# 8_Motors_sch.net
KiCad netlist of a schematic drawn in Altium Designer
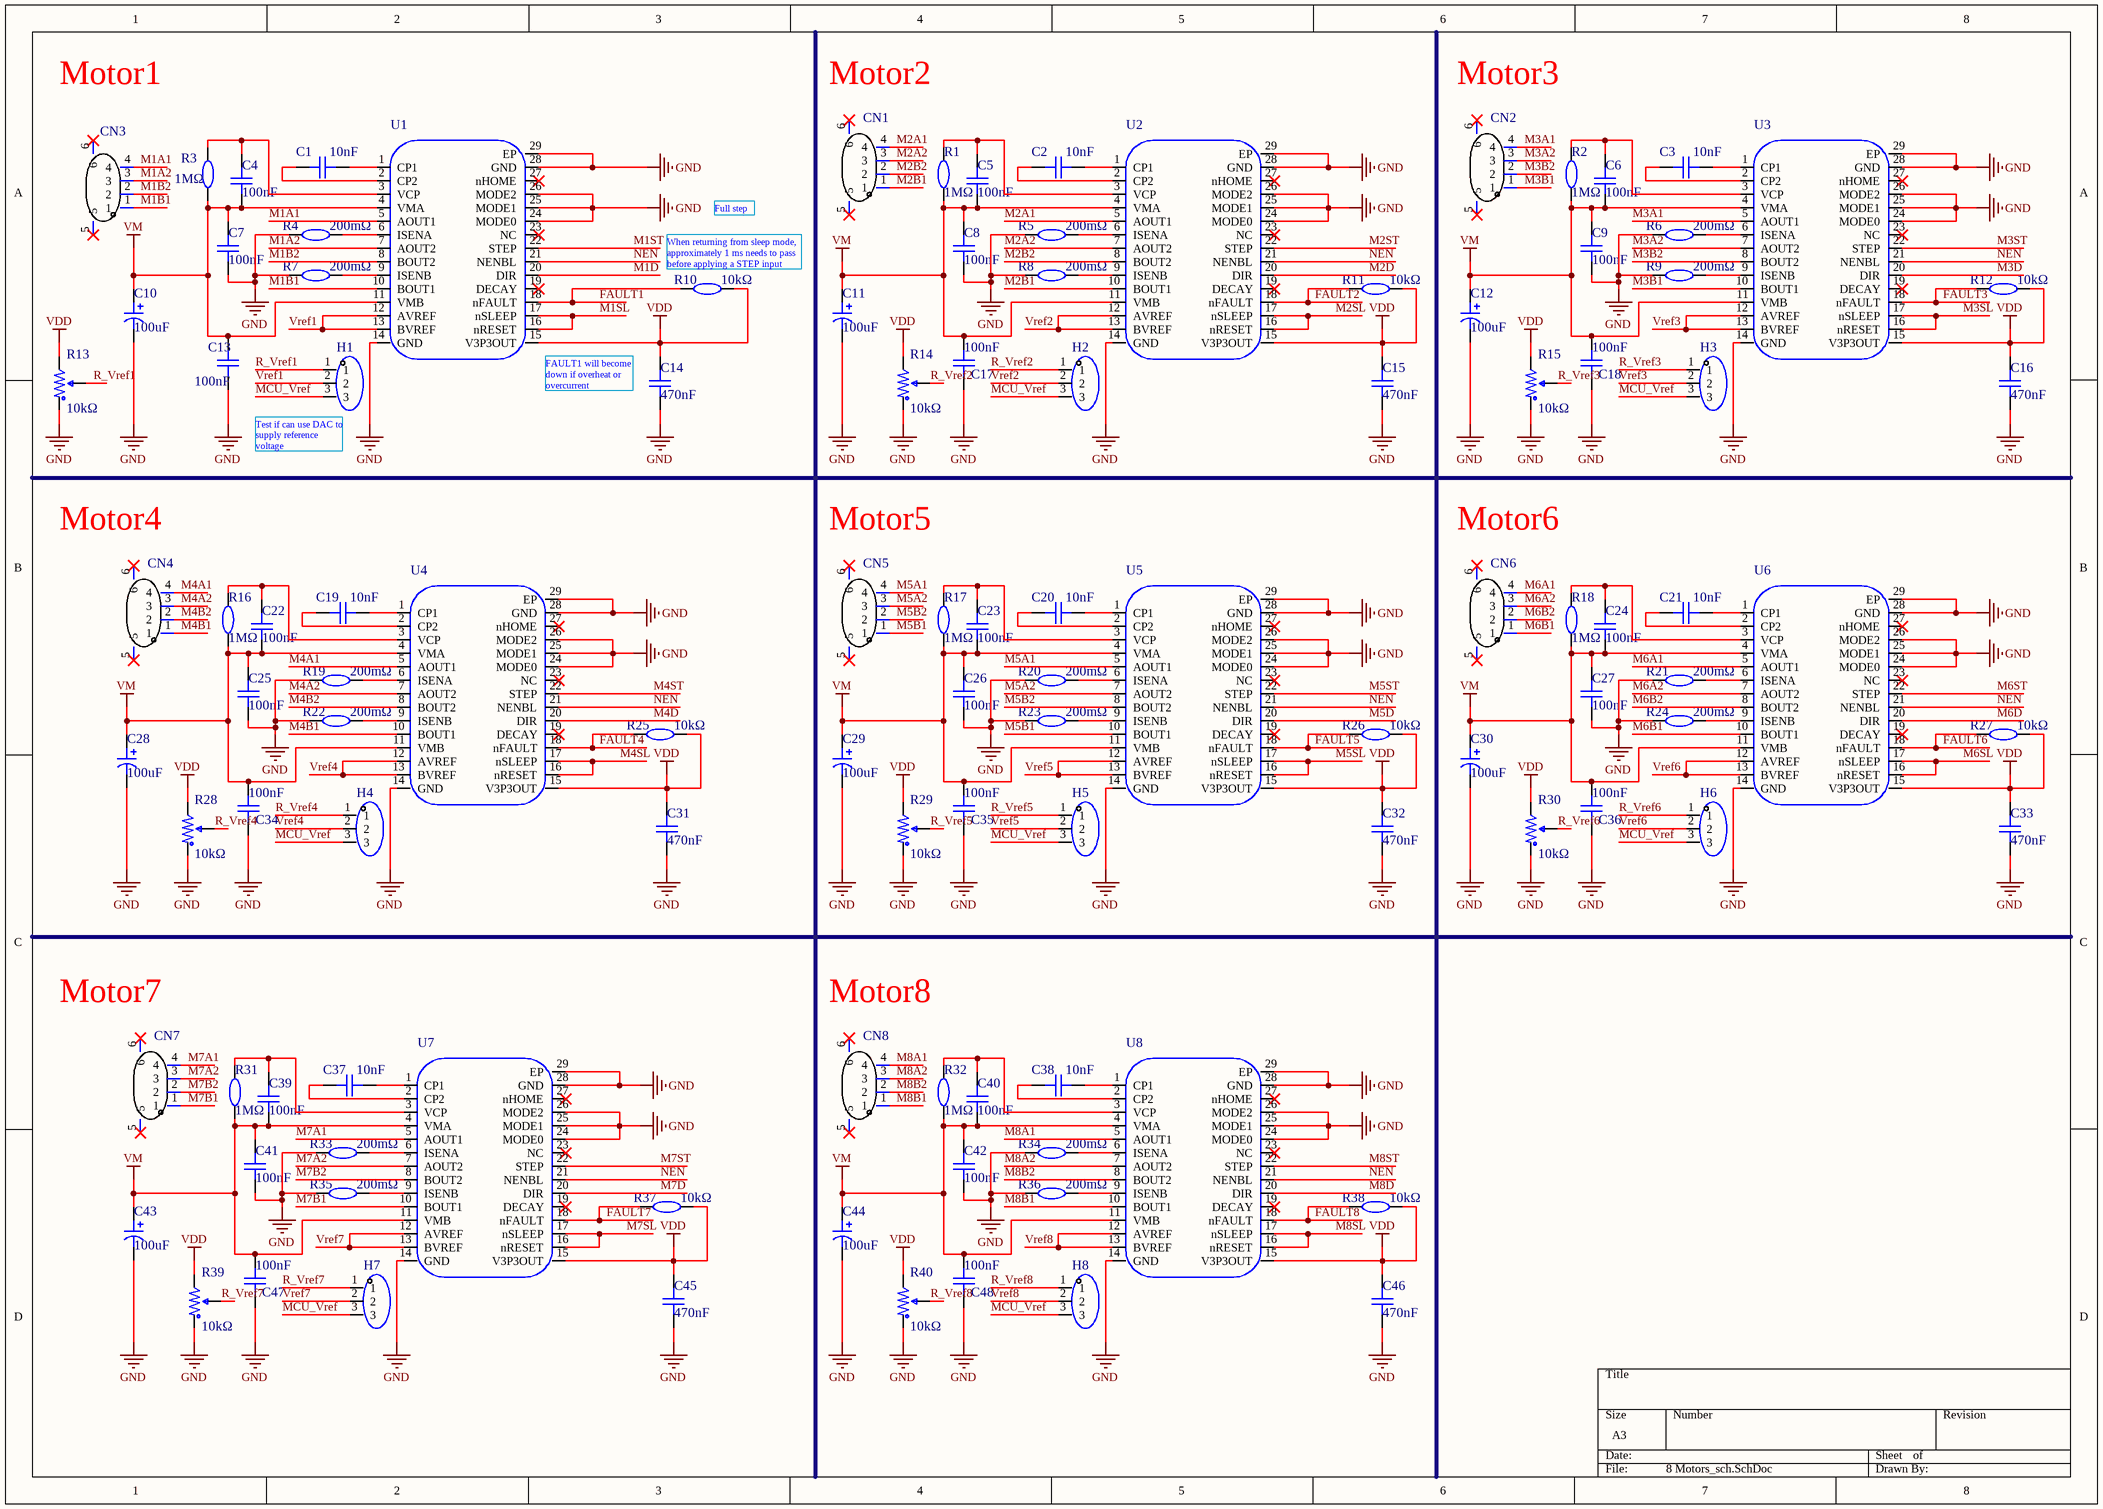
[diagram p0: 8 Motors_sch.SchDoc]

(export (version "E")
  (design (tool "Eeschema 10.0.6"))
  (components
    (comp (ref "C1")
      (value "10nF")
      (footprint "C0603")
      (description "0603电容")
      (fields
        (field (name "MANUFACTURER") "SAMSUNG(三星)")
        (field (name "MANUFACTURER PART") "CC0603KRX7R9BB104")
      )
      (libsource (lib "SchLib") (part "C0603_10nF"))
    )
    (comp (ref "C2")
      (value "10nF")
      (footprint "C0603")
      (description "0603电容")
      (fields
        (field (name "MANUFACTURER") "SAMSUNG(三星)")
        (field (name "MANUFACTURER PART") "CC0603KRX7R9BB104")
      )
      (libsource (lib "SchLib") (part "C0603_10nF"))
    )
    (comp (ref "C3")
      (value "10nF")
      (footprint "C0603")
      (description "0603电容")
      (fields
        (field (name "MANUFACTURER") "SAMSUNG(三星)")
        (field (name "MANUFACTURER PART") "CC0603KRX7R9BB104")
      )
      (libsource (lib "SchLib") (part "C0603_10nF"))
    )
    (comp (ref "C4")
      (value "100nF")
      (footprint "C0603")
      (description "0603电容")
      (fields
        (field (name "MANUFACTURER") "SAMSUNG(三星)")
        (field (name "MANUFACTURER PART") "CC0603KRX7R9BB104")
      )
      (libsource (lib "SchLib") (part "C0603_100nF"))
    )
    (comp (ref "C5")
      (value "100nF")
      (footprint "C0603")
      (description "0603电容")
      (fields
        (field (name "MANUFACTURER") "SAMSUNG(三星)")
        (field (name "MANUFACTURER PART") "CC0603KRX7R9BB104")
      )
      (libsource (lib "SchLib") (part "C0603_100nF"))
    )
    (comp (ref "C6")
      (value "100nF")
      (footprint "C0603")
      (description "0603电容")
      (fields
        (field (name "MANUFACTURER") "SAMSUNG(三星)")
        (field (name "MANUFACTURER PART") "CC0603KRX7R9BB104")
      )
      (libsource (lib "SchLib") (part "C0603_100nF"))
    )
    (comp (ref "C7")
      (value "100nF")
      (footprint "C0603")
      (description "0603电容")
      (fields
        (field (name "MANUFACTURER") "SAMSUNG(三星)")
        (field (name "MANUFACTURER PART") "CC0603KRX7R9BB104")
      )
      (libsource (lib "SchLib") (part "C0603_100nF"))
    )
    (comp (ref "C8")
      (value "100nF")
      (footprint "C0603")
      (description "0603电容")
      (fields
        (field (name "MANUFACTURER") "SAMSUNG(三星)")
        (field (name "MANUFACTURER PART") "CC0603KRX7R9BB104")
      )
      (libsource (lib "SchLib") (part "C0603_100nF"))
    )
    (comp (ref "C9")
      (value "100nF")
      (footprint "C0603")
      (description "0603电容")
      (fields
        (field (name "MANUFACTURER") "SAMSUNG(三星)")
        (field (name "MANUFACTURER PART") "CC0603KRX7R9BB104")
      )
      (libsource (lib "SchLib") (part "C0603_100nF"))
    )
    (comp (ref "C10")
      (value "100uF")
      (footprint "SMD6.3_7.7_100uF")
      (description "贴片型铝电解电容 容值 100uF 精度 ±20% 额定电压 35V 纹波电流 87mA@120kHz")
      (fields
        (field (name "MANUFACTURER") "KNSCHA(科尼盛)")
        (field (name "MANUFACTURER PART") "RVT100UF35V67RV0034")
      )
      (libsource (lib "SchLib") (part "SMD6.3_7.7_100uF"))
    )
    (comp (ref "C11")
      (value "100uF")
      (footprint "SMD6.3_7.7_100uF")
      (description "贴片型铝电解电容 容值 100uF 精度 ±20% 额定电压 35V 纹波电流 87mA@120kHz")
      (fields
        (field (name "MANUFACTURER") "KNSCHA(科尼盛)")
        (field (name "MANUFACTURER PART") "RVT100UF35V67RV0034")
      )
      (libsource (lib "SchLib") (part "SMD6.3_7.7_100uF"))
    )
    (comp (ref "C12")
      (value "100uF")
      (footprint "SMD6.3_7.7_100uF")
      (description "贴片型铝电解电容 容值 100uF 精度 ±20% 额定电压 35V 纹波电流 87mA@120kHz")
      (fields
        (field (name "MANUFACTURER") "KNSCHA(科尼盛)")
        (field (name "MANUFACTURER PART") "RVT100UF35V67RV0034")
      )
      (libsource (lib "SchLib") (part "SMD6.3_7.7_100uF"))
    )
    (comp (ref "C13")
      (value "100nF")
      (footprint "C0603")
      (description "0603电容")
      (fields
        (field (name "MANUFACTURER") "SAMSUNG(三星)")
        (field (name "MANUFACTURER PART") "CC0603KRX7R9BB104")
      )
      (libsource (lib "SchLib") (part "C0603_100nF"))
    )
    (comp (ref "C14")
      (value "470nF")
      (footprint "C0603")
      (description "0603电容")
      (fields
        (field (name "MANUFACTURER") "SAMSUNG(三星)")
        (field (name "MANUFACTURER PART") "CC0603KRX7R9BB104")
      )
      (libsource (lib "SchLib") (part "C0603_470nF"))
    )
    (comp (ref "C15")
      (value "470nF")
      (footprint "C0603")
      (description "0603电容")
      (fields
        (field (name "MANUFACTURER") "SAMSUNG(三星)")
        (field (name "MANUFACTURER PART") "CC0603KRX7R9BB104")
      )
      (libsource (lib "SchLib") (part "C0603_470nF"))
    )
    (comp (ref "C16")
      (value "470nF")
      (footprint "C0603")
      (description "0603电容")
      (fields
        (field (name "MANUFACTURER") "SAMSUNG(三星)")
        (field (name "MANUFACTURER PART") "CC0603KRX7R9BB104")
      )
      (libsource (lib "SchLib") (part "C0603_470nF"))
    )
    (comp (ref "C17")
      (value "100nF")
      (footprint "C0603")
      (description "0603电容")
      (fields
        (field (name "MANUFACTURER") "SAMSUNG(三星)")
        (field (name "MANUFACTURER PART") "CC0603KRX7R9BB104")
      )
      (libsource (lib "SchLib") (part "C0603_100nF"))
    )
    (comp (ref "C18")
      (value "100nF")
      (footprint "C0603")
      (description "0603电容")
      (fields
        (field (name "MANUFACTURER") "SAMSUNG(三星)")
        (field (name "MANUFACTURER PART") "CC0603KRX7R9BB104")
      )
      (libsource (lib "SchLib") (part "C0603_100nF"))
    )
    (comp (ref "C19")
      (value "10nF")
      (footprint "C0603")
      (description "0603电容")
      (fields
        (field (name "MANUFACTURER") "SAMSUNG(三星)")
        (field (name "MANUFACTURER PART") "CC0603KRX7R9BB104")
      )
      (libsource (lib "SchLib") (part "C0603_10nF"))
    )
    (comp (ref "C20")
      (value "10nF")
      (footprint "C0603")
      (description "0603电容")
      (fields
        (field (name "MANUFACTURER") "SAMSUNG(三星)")
        (field (name "MANUFACTURER PART") "CC0603KRX7R9BB104")
      )
      (libsource (lib "SchLib") (part "C0603_10nF"))
    )
    (comp (ref "C21")
      (value "10nF")
      (footprint "C0603")
      (description "0603电容")
      (fields
        (field (name "MANUFACTURER") "SAMSUNG(三星)")
        (field (name "MANUFACTURER PART") "CC0603KRX7R9BB104")
      )
      (libsource (lib "SchLib") (part "C0603_10nF"))
    )
    (comp (ref "C22")
      (value "100nF")
      (footprint "C0603")
      (description "0603电容")
      (fields
        (field (name "MANUFACTURER") "SAMSUNG(三星)")
        (field (name "MANUFACTURER PART") "CC0603KRX7R9BB104")
      )
      (libsource (lib "SchLib") (part "C0603_100nF"))
    )
    (comp (ref "C23")
      (value "100nF")
      (footprint "C0603")
      (description "0603电容")
      (fields
        (field (name "MANUFACTURER") "SAMSUNG(三星)")
        (field (name "MANUFACTURER PART") "CC0603KRX7R9BB104")
      )
      (libsource (lib "SchLib") (part "C0603_100nF"))
    )
    (comp (ref "C24")
      (value "100nF")
      (footprint "C0603")
      (description "0603电容")
      (fields
        (field (name "MANUFACTURER") "SAMSUNG(三星)")
        (field (name "MANUFACTURER PART") "CC0603KRX7R9BB104")
      )
      (libsource (lib "SchLib") (part "C0603_100nF"))
    )
    (comp (ref "C25")
      (value "100nF")
      (footprint "C0603")
      (description "0603电容")
      (fields
        (field (name "MANUFACTURER") "SAMSUNG(三星)")
        (field (name "MANUFACTURER PART") "CC0603KRX7R9BB104")
      )
      (libsource (lib "SchLib") (part "C0603_100nF"))
    )
    (comp (ref "C26")
      (value "100nF")
      (footprint "C0603")
      (description "0603电容")
      (fields
        (field (name "MANUFACTURER") "SAMSUNG(三星)")
        (field (name "MANUFACTURER PART") "CC0603KRX7R9BB104")
      )
      (libsource (lib "SchLib") (part "C0603_100nF"))
    )
    (comp (ref "C27")
      (value "100nF")
      (footprint "C0603")
      (description "0603电容")
      (fields
        (field (name "MANUFACTURER") "SAMSUNG(三星)")
        (field (name "MANUFACTURER PART") "CC0603KRX7R9BB104")
      )
      (libsource (lib "SchLib") (part "C0603_100nF"))
    )
    (comp (ref "C28")
      (value "100uF")
      (footprint "SMD6.3_7.7_100uF")
      (description "贴片型铝电解电容 容值 100uF 精度 ±20% 额定电压 35V 纹波电流 87mA@120kHz")
      (fields
        (field (name "MANUFACTURER") "KNSCHA(科尼盛)")
        (field (name "MANUFACTURER PART") "RVT100UF35V67RV0034")
      )
      (libsource (lib "SchLib") (part "SMD6.3_7.7_100uF"))
    )
    (comp (ref "C29")
      (value "100uF")
      (footprint "SMD6.3_7.7_100uF")
      (description "贴片型铝电解电容 容值 100uF 精度 ±20% 额定电压 35V 纹波电流 87mA@120kHz")
      (fields
        (field (name "MANUFACTURER") "KNSCHA(科尼盛)")
        (field (name "MANUFACTURER PART") "RVT100UF35V67RV0034")
      )
      (libsource (lib "SchLib") (part "SMD6.3_7.7_100uF"))
    )
    (comp (ref "C30")
      (value "100uF")
      (footprint "SMD6.3_7.7_100uF")
      (description "贴片型铝电解电容 容值 100uF 精度 ±20% 额定电压 35V 纹波电流 87mA@120kHz")
      (fields
        (field (name "MANUFACTURER") "KNSCHA(科尼盛)")
        (field (name "MANUFACTURER PART") "RVT100UF35V67RV0034")
      )
      (libsource (lib "SchLib") (part "SMD6.3_7.7_100uF"))
    )
    (comp (ref "C31")
      (value "470nF")
      (footprint "C0603")
      (description "0603电容")
      (fields
        (field (name "MANUFACTURER") "SAMSUNG(三星)")
        (field (name "MANUFACTURER PART") "CC0603KRX7R9BB104")
      )
      (libsource (lib "SchLib") (part "C0603_470nF"))
    )
    (comp (ref "C32")
      (value "470nF")
      (footprint "C0603")
      (description "0603电容")
      (fields
        (field (name "MANUFACTURER") "SAMSUNG(三星)")
        (field (name "MANUFACTURER PART") "CC0603KRX7R9BB104")
      )
      (libsource (lib "SchLib") (part "C0603_470nF"))
    )
    (comp (ref "C33")
      (value "470nF")
      (footprint "C0603")
      (description "0603电容")
      (fields
        (field (name "MANUFACTURER") "SAMSUNG(三星)")
        (field (name "MANUFACTURER PART") "CC0603KRX7R9BB104")
      )
      (libsource (lib "SchLib") (part "C0603_470nF"))
    )
    (comp (ref "C34")
      (value "100nF")
      (footprint "C0603")
      (description "0603电容")
      (fields
        (field (name "MANUFACTURER") "SAMSUNG(三星)")
        (field (name "MANUFACTURER PART") "CC0603KRX7R9BB104")
      )
      (libsource (lib "SchLib") (part "C0603_100nF"))
    )
    (comp (ref "C35")
      (value "100nF")
      (footprint "C0603")
      (description "0603电容")
      (fields
        (field (name "MANUFACTURER") "SAMSUNG(三星)")
        (field (name "MANUFACTURER PART") "CC0603KRX7R9BB104")
      )
      (libsource (lib "SchLib") (part "C0603_100nF"))
    )
    (comp (ref "C36")
      (value "100nF")
      (footprint "C0603")
      (description "0603电容")
      (fields
        (field (name "MANUFACTURER") "SAMSUNG(三星)")
        (field (name "MANUFACTURER PART") "CC0603KRX7R9BB104")
      )
      (libsource (lib "SchLib") (part "C0603_100nF"))
    )
    (comp (ref "C37")
      (value "10nF")
      (footprint "C0603")
      (description "0603电容")
      (fields
        (field (name "MANUFACTURER") "SAMSUNG(三星)")
        (field (name "MANUFACTURER PART") "CC0603KRX7R9BB104")
      )
      (libsource (lib "SchLib") (part "C0603_10nF"))
    )
    (comp (ref "C38")
      (value "10nF")
      (footprint "C0603")
      (description "0603电容")
      (fields
        (field (name "MANUFACTURER") "SAMSUNG(三星)")
        (field (name "MANUFACTURER PART") "CC0603KRX7R9BB104")
      )
      (libsource (lib "SchLib") (part "C0603_10nF"))
    )
    (comp (ref "C39")
      (value "100nF")
      (footprint "C0603")
      (description "0603电容")
      (fields
        (field (name "MANUFACTURER") "SAMSUNG(三星)")
        (field (name "MANUFACTURER PART") "CC0603KRX7R9BB104")
      )
      (libsource (lib "SchLib") (part "C0603_100nF"))
    )
    (comp (ref "C40")
      (value "100nF")
      (footprint "C0603")
      (description "0603电容")
      (fields
        (field (name "MANUFACTURER") "SAMSUNG(三星)")
        (field (name "MANUFACTURER PART") "CC0603KRX7R9BB104")
      )
      (libsource (lib "SchLib") (part "C0603_100nF"))
    )
    (comp (ref "C41")
      (value "100nF")
      (footprint "C0603")
      (description "0603电容")
      (fields
        (field (name "MANUFACTURER") "SAMSUNG(三星)")
        (field (name "MANUFACTURER PART") "CC0603KRX7R9BB104")
      )
      (libsource (lib "SchLib") (part "C0603_100nF"))
    )
    (comp (ref "C42")
      (value "100nF")
      (footprint "C0603")
      (description "0603电容")
      (fields
        (field (name "MANUFACTURER") "SAMSUNG(三星)")
        (field (name "MANUFACTURER PART") "CC0603KRX7R9BB104")
      )
      (libsource (lib "SchLib") (part "C0603_100nF"))
    )
    (comp (ref "C43")
      (value "100uF")
      (footprint "SMD6.3_7.7_100uF")
      (description "贴片型铝电解电容 容值 100uF 精度 ±20% 额定电压 35V 纹波电流 87mA@120kHz")
      (fields
        (field (name "MANUFACTURER") "KNSCHA(科尼盛)")
        (field (name "MANUFACTURER PART") "RVT100UF35V67RV0034")
      )
      (libsource (lib "SchLib") (part "SMD6.3_7.7_100uF"))
    )
    (comp (ref "C44")
      (value "100uF")
      (footprint "SMD6.3_7.7_100uF")
      (description "贴片型铝电解电容 容值 100uF 精度 ±20% 额定电压 35V 纹波电流 87mA@120kHz")
      (fields
        (field (name "MANUFACTURER") "KNSCHA(科尼盛)")
        (field (name "MANUFACTURER PART") "RVT100UF35V67RV0034")
      )
      (libsource (lib "SchLib") (part "SMD6.3_7.7_100uF"))
    )
    (comp (ref "C45")
      (value "470nF")
      (footprint "C0603")
      (description "0603电容")
      (fields
        (field (name "MANUFACTURER") "SAMSUNG(三星)")
        (field (name "MANUFACTURER PART") "CC0603KRX7R9BB104")
      )
      (libsource (lib "SchLib") (part "C0603_470nF"))
    )
    (comp (ref "C46")
      (value "470nF")
      (footprint "C0603")
      (description "0603电容")
      (fields
        (field (name "MANUFACTURER") "SAMSUNG(三星)")
        (field (name "MANUFACTURER PART") "CC0603KRX7R9BB104")
      )
      (libsource (lib "SchLib") (part "C0603_470nF"))
    )
    (comp (ref "C47")
      (value "100nF")
      (footprint "C0603")
      (description "0603电容")
      (fields
        (field (name "MANUFACTURER") "SAMSUNG(三星)")
        (field (name "MANUFACTURER PART") "CC0603KRX7R9BB104")
      )
      (libsource (lib "SchLib") (part "C0603_100nF"))
    )
    (comp (ref "C48")
      (value "100nF")
      (footprint "C0603")
      (description "0603电容")
      (fields
        (field (name "MANUFACTURER") "SAMSUNG(三星)")
        (field (name "MANUFACTURER PART") "CC0603KRX7R9BB104")
      )
      (libsource (lib "SchLib") (part "C0603_100nF"))
    )
    (comp (ref "CN1")
      (value "HC-1.25-4PLT")
      (footprint "HC-1.25-4PLT")
      (description "插针结构: 1x4P  间距: 1.25mm  安装方式: 立贴  总PIN数: 4P")
      (fields (field (name "MANUFACTURER") "HCTL(华灿天禄)"))
      (libsource (lib "SchLib") (part "HC-1.25-4PLT"))
    )
    (comp (ref "CN2")
      (value "HC-1.25-4PLT")
      (footprint "HC-1.25-4PLT")
      (description "插针结构: 1x4P  间距: 1.25mm  安装方式: 立贴  总PIN数: 4P")
      (fields (field (name "MANUFACTURER") "HCTL(华灿天禄)"))
      (libsource (lib "SchLib") (part "HC-1.25-4PLT"))
    )
    (comp (ref "CN3")
      (value "HC-1.25-4PLT")
      (footprint "HC-1.25-4PLT")
      (description "插针结构: 1x4P  间距: 1.25mm  安装方式: 立贴  总PIN数: 4P")
      (fields (field (name "MANUFACTURER") "HCTL(华灿天禄)"))
      (libsource (lib "SchLib") (part "HC-1.25-4PLT"))
    )
    (comp (ref "CN4")
      (value "HC-1.25-4PLT")
      (footprint "HC-1.25-4PLT")
      (description "插针结构: 1x4P  间距: 1.25mm  安装方式: 立贴  总PIN数: 4P")
      (fields (field (name "MANUFACTURER") "HCTL(华灿天禄)"))
      (libsource (lib "SchLib") (part "HC-1.25-4PLT"))
    )
    (comp (ref "CN5")
      (value "HC-1.25-4PLT")
      (footprint "HC-1.25-4PLT")
      (description "插针结构: 1x4P  间距: 1.25mm  安装方式: 立贴  总PIN数: 4P")
      (fields (field (name "MANUFACTURER") "HCTL(华灿天禄)"))
      (libsource (lib "SchLib") (part "HC-1.25-4PLT"))
    )
    (comp (ref "CN6")
      (value "HC-1.25-4PLT")
      (footprint "HC-1.25-4PLT")
      (description "插针结构: 1x4P  间距: 1.25mm  安装方式: 立贴  总PIN数: 4P")
      (fields (field (name "MANUFACTURER") "HCTL(华灿天禄)"))
      (libsource (lib "SchLib") (part "HC-1.25-4PLT"))
    )
    (comp (ref "CN7")
      (value "HC-1.25-4PLT")
      (footprint "HC-1.25-4PLT")
      (description "插针结构: 1x4P  间距: 1.25mm  安装方式: 立贴  总PIN数: 4P")
      (fields (field (name "MANUFACTURER") "HCTL(华灿天禄)"))
      (libsource (lib "SchLib") (part "HC-1.25-4PLT"))
    )
    (comp (ref "CN8")
      (value "HC-1.25-4PLT")
      (footprint "HC-1.25-4PLT")
      (description "插针结构: 1x4P  间距: 1.25mm  安装方式: 立贴  总PIN数: 4P")
      (fields (field (name "MANUFACTURER") "HCTL(华灿天禄)"))
      (libsource (lib "SchLib") (part "HC-1.25-4PLT"))
    )
    (comp (ref "H1")
      (value "PZ254V-11-03P")
      (footprint "HC-1.25-3PLT")
      (description "排针3P")
      (fields (field (name "MANUFACTURER") "XFCN(兴飞)"))
      (libsource (lib "SchLib") (part "HC-1.25-3PLT"))
    )
    (comp (ref "H2")
      (value "PZ254V-11-03P")
      (footprint "HC-1.25-3PLT")
      (description "排针3P")
      (fields (field (name "MANUFACTURER") "XFCN(兴飞)"))
      (libsource (lib "SchLib") (part "HC-1.25-3PLT"))
    )
    (comp (ref "H3")
      (value "PZ254V-11-03P")
      (footprint "HC-1.25-3PLT")
      (description "排针3P")
      (fields (field (name "MANUFACTURER") "XFCN(兴飞)"))
      (libsource (lib "SchLib") (part "HC-1.25-3PLT"))
    )
    (comp (ref "H4")
      (value "PZ254V-11-03P")
      (footprint "HC-1.25-3PLT")
      (description "排针3P")
      (fields (field (name "MANUFACTURER") "XFCN(兴飞)"))
      (libsource (lib "SchLib") (part "HC-1.25-3PLT"))
    )
    (comp (ref "H5")
      (value "PZ254V-11-03P")
      (footprint "HC-1.25-3PLT")
      (description "排针3P")
      (fields (field (name "MANUFACTURER") "XFCN(兴飞)"))
      (libsource (lib "SchLib") (part "HC-1.25-3PLT"))
    )
    (comp (ref "H6")
      (value "PZ254V-11-03P")
      (footprint "HC-1.25-3PLT")
      (description "排针3P")
      (fields (field (name "MANUFACTURER") "XFCN(兴飞)"))
      (libsource (lib "SchLib") (part "HC-1.25-3PLT"))
    )
    (comp (ref "H7")
      (value "PZ254V-11-03P")
      (footprint "HC-1.25-3PLT")
      (description "排针3P")
      (fields (field (name "MANUFACTURER") "XFCN(兴飞)"))
      (libsource (lib "SchLib") (part "HC-1.25-3PLT"))
    )
    (comp (ref "H8")
      (value "PZ254V-11-03P")
      (footprint "HC-1.25-3PLT")
      (description "排针3P")
      (fields (field (name "MANUFACTURER") "XFCN(兴飞)"))
      (libsource (lib "SchLib") (part "HC-1.25-3PLT"))
    )
    (comp (ref "R1")
      (value "1MΩ")
      (footprint "R0603")
      (description "0603电阻")
      (fields
        (field (name "MANUFACTURER") "UNI-ROYAL(厚声)")
        (field (name "MANUFACTURER PART") "0603WAF5100T5E")
      )
      (libsource (lib "SchLib") (part "R0603_1MΩ"))
    )
    (comp (ref "R2")
      (value "1MΩ")
      (footprint "R0603")
      (description "0603电阻")
      (fields
        (field (name "MANUFACTURER") "UNI-ROYAL(厚声)")
        (field (name "MANUFACTURER PART") "0603WAF5100T5E")
      )
      (libsource (lib "SchLib") (part "R0603_1MΩ"))
    )
    (comp (ref "R3")
      (value "1MΩ")
      (footprint "R0603")
      (description "0603电阻")
      (fields
        (field (name "MANUFACTURER") "UNI-ROYAL(厚声)")
        (field (name "MANUFACTURER PART") "0603WAF5100T5E")
      )
      (libsource (lib "SchLib") (part "R0603_1MΩ"))
    )
    (comp (ref "R4")
      (value "200mΩ")
      (footprint "R1206_200mΩ")
      (description "1206电阻")
      (fields
        (field (name "MANUFACTURER") "UNI-ROYAL(厚声)")
        (field (name "MANUFACTURER PART") "1206W4F200LT5E")
      )
      (libsource (lib "SchLib") (part "R1206_200mΩ"))
    )
    (comp (ref "R5")
      (value "200mΩ")
      (footprint "R1206_200mΩ")
      (description "1206电阻")
      (fields
        (field (name "MANUFACTURER") "UNI-ROYAL(厚声)")
        (field (name "MANUFACTURER PART") "1206W4F200LT5E")
      )
      (libsource (lib "SchLib") (part "R1206_200mΩ"))
    )
    (comp (ref "R6")
      (value "200mΩ")
      (footprint "R1206_200mΩ")
      (description "1206电阻")
      (fields
        (field (name "MANUFACTURER") "UNI-ROYAL(厚声)")
        (field (name "MANUFACTURER PART") "1206W4F200LT5E")
      )
      (libsource (lib "SchLib") (part "R1206_200mΩ"))
    )
    (comp (ref "R7")
      (value "200mΩ")
      (footprint "R1206_200mΩ")
      (description "1206电阻")
      (fields
        (field (name "MANUFACTURER") "UNI-ROYAL(厚声)")
        (field (name "MANUFACTURER PART") "1206W4F200LT5E")
      )
      (libsource (lib "SchLib") (part "R1206_200mΩ"))
    )
    (comp (ref "R8")
      (value "200mΩ")
      (footprint "R1206_200mΩ")
      (description "1206电阻")
      (fields
        (field (name "MANUFACTURER") "UNI-ROYAL(厚声)")
        (field (name "MANUFACTURER PART") "1206W4F200LT5E")
      )
      (libsource (lib "SchLib") (part "R1206_200mΩ"))
    )
    (comp (ref "R9")
      (value "200mΩ")
      (footprint "R1206_200mΩ")
      (description "1206电阻")
      (fields
        (field (name "MANUFACTURER") "UNI-ROYAL(厚声)")
        (field (name "MANUFACTURER PART") "1206W4F200LT5E")
      )
      (libsource (lib "SchLib") (part "R1206_200mΩ"))
    )
    (comp (ref "R10")
      (value "10kΩ")
      (footprint "R0603_10KΩ")
      (description "0603电阻")
      (fields
        (field (name "MANUFACTURER") "UNI-ROYAL(厚声)")
        (field (name "MANUFACTURER PART") "0603WAF1002T5E")
      )
      (libsource (lib "SchLib") (part "R0603_10KΩ"))
    )
    (comp (ref "R11")
      (value "10kΩ")
      (footprint "R0603_10KΩ")
      (description "0603电阻")
      (fields
        (field (name "MANUFACTURER") "UNI-ROYAL(厚声)")
        (field (name "MANUFACTURER PART") "0603WAF1002T5E")
      )
      (libsource (lib "SchLib") (part "R0603_10KΩ"))
    )
    (comp (ref "R12")
      (value "10kΩ")
      (footprint "R0603_10KΩ")
      (description "0603电阻")
      (fields
        (field (name "MANUFACTURER") "UNI-ROYAL(厚声)")
        (field (name "MANUFACTURER PART") "0603WAF1002T5E")
      )
      (libsource (lib "SchLib") (part "R0603_10KΩ"))
    )
    (comp (ref "R13")
      (value "10kΩ")
      (footprint "R10k_KT")
      (description "可调电阻/电位器   阻值 10kΩ   精度 ±25%   额定电压 -   功率 150mW   温度系数 ±250ppm/℃   圈数 1")
      (fields (field (name "MANUFACTURER") "BOURNS") (field (name "MANUFACTURER PART") "TC33X-2-103E"))
      (libsource (lib "SchLib") (part "R10k_KT"))
    )
    (comp (ref "R14")
      (value "10kΩ")
      (footprint "R10k_KT")
      (description "可调电阻/电位器   阻值 10kΩ   精度 ±25%   额定电压 -   功率 150mW   温度系数 ±250ppm/℃   圈数 1")
      (fields (field (name "MANUFACTURER") "BOURNS") (field (name "MANUFACTURER PART") "TC33X-2-103E"))
      (libsource (lib "SchLib") (part "R10k_KT"))
    )
    (comp (ref "R15")
      (value "10kΩ")
      (footprint "R10k_KT")
      (description "可调电阻/电位器   阻值 10kΩ   精度 ±25%   额定电压 -   功率 150mW   温度系数 ±250ppm/℃   圈数 1")
      (fields (field (name "MANUFACTURER") "BOURNS") (field (name "MANUFACTURER PART") "TC33X-2-103E"))
      (libsource (lib "SchLib") (part "R10k_KT"))
    )
    (comp (ref "R16")
      (value "1MΩ")
      (footprint "R0603")
      (description "0603电阻")
      (fields
        (field (name "MANUFACTURER") "UNI-ROYAL(厚声)")
        (field (name "MANUFACTURER PART") "0603WAF5100T5E")
      )
      (libsource (lib "SchLib") (part "R0603_1MΩ"))
    )
    (comp (ref "R17")
      (value "1MΩ")
      (footprint "R0603")
      (description "0603电阻")
      (fields
        (field (name "MANUFACTURER") "UNI-ROYAL(厚声)")
        (field (name "MANUFACTURER PART") "0603WAF5100T5E")
      )
      (libsource (lib "SchLib") (part "R0603_1MΩ"))
    )
    (comp (ref "R18")
      (value "1MΩ")
      (footprint "R0603")
      (description "0603电阻")
      (fields
        (field (name "MANUFACTURER") "UNI-ROYAL(厚声)")
        (field (name "MANUFACTURER PART") "0603WAF5100T5E")
      )
      (libsource (lib "SchLib") (part "R0603_1MΩ"))
    )
    (comp (ref "R19")
      (value "200mΩ")
      (footprint "R1206_200mΩ")
      (description "1206电阻")
      (fields
        (field (name "MANUFACTURER") "UNI-ROYAL(厚声)")
        (field (name "MANUFACTURER PART") "1206W4F200LT5E")
      )
      (libsource (lib "SchLib") (part "R1206_200mΩ"))
    )
    (comp (ref "R20")
      (value "200mΩ")
      (footprint "R1206_200mΩ")
      (description "1206电阻")
      (fields
        (field (name "MANUFACTURER") "UNI-ROYAL(厚声)")
        (field (name "MANUFACTURER PART") "1206W4F200LT5E")
      )
      (libsource (lib "SchLib") (part "R1206_200mΩ"))
    )
    (comp (ref "R21")
      (value "200mΩ")
      (footprint "R1206_200mΩ")
      (description "1206电阻")
      (fields
        (field (name "MANUFACTURER") "UNI-ROYAL(厚声)")
        (field (name "MANUFACTURER PART") "1206W4F200LT5E")
      )
      (libsource (lib "SchLib") (part "R1206_200mΩ"))
    )
    (comp (ref "R22")
      (value "200mΩ")
      (footprint "R1206_200mΩ")
      (description "1206电阻")
      (fields
        (field (name "MANUFACTURER") "UNI-ROYAL(厚声)")
        (field (name "MANUFACTURER PART") "1206W4F200LT5E")
      )
      (libsource (lib "SchLib") (part "R1206_200mΩ"))
    )
    (comp (ref "R23")
      (value "200mΩ")
      (footprint "R1206_200mΩ")
      (description "1206电阻")
      (fields
        (field (name "MANUFACTURER") "UNI-ROYAL(厚声)")
        (field (name "MANUFACTURER PART") "1206W4F200LT5E")
      )
      (libsource (lib "SchLib") (part "R1206_200mΩ"))
    )
    (comp (ref "R24")
      (value "200mΩ")
      (footprint "R1206_200mΩ")
      (description "1206电阻")
      (fields
        (field (name "MANUFACTURER") "UNI-ROYAL(厚声)")
        (field (name "MANUFACTURER PART") "1206W4F200LT5E")
      )
      (libsource (lib "SchLib") (part "R1206_200mΩ"))
    )
    (comp (ref "R25")
      (value "10kΩ")
      (footprint "R0603_10KΩ")
      (description "0603电阻")
      (fields
        (field (name "MANUFACTURER") "UNI-ROYAL(厚声)")
        (field (name "MANUFACTURER PART") "0603WAF1002T5E")
      )
      (libsource (lib "SchLib") (part "R0603_10KΩ"))
    )
    (comp (ref "R26")
      (value "10kΩ")
      (footprint "R0603_10KΩ")
      (description "0603电阻")
      (fields
        (field (name "MANUFACTURER") "UNI-ROYAL(厚声)")
        (field (name "MANUFACTURER PART") "0603WAF1002T5E")
      )
      (libsource (lib "SchLib") (part "R0603_10KΩ"))
    )
    (comp (ref "R27")
      (value "10kΩ")
      (footprint "R0603_10KΩ")
      (description "0603电阻")
      (fields
        (field (name "MANUFACTURER") "UNI-ROYAL(厚声)")
        (field (name "MANUFACTURER PART") "0603WAF1002T5E")
      )
      (libsource (lib "SchLib") (part "R0603_10KΩ"))
    )
    (comp (ref "R28")
      (value "10kΩ")
      (footprint "R10k_KT")
      (description "可调电阻/电位器   阻值 10kΩ   精度 ±25%   额定电压 -   功率 150mW   温度系数 ±250ppm/℃   圈数 1")
      (fields (field (name "MANUFACTURER") "BOURNS") (field (name "MANUFACTURER PART") "TC33X-2-103E"))
      (libsource (lib "SchLib") (part "R10k_KT"))
    )
    (comp (ref "R29")
      (value "10kΩ")
      (footprint "R10k_KT")
      (description "可调电阻/电位器   阻值 10kΩ   精度 ±25%   额定电压 -   功率 150mW   温度系数 ±250ppm/℃   圈数 1")
      (fields (field (name "MANUFACTURER") "BOURNS") (field (name "MANUFACTURER PART") "TC33X-2-103E"))
      (libsource (lib "SchLib") (part "R10k_KT"))
    )
    (comp (ref "R30")
      (value "10kΩ")
      (footprint "R10k_KT")
      (description "可调电阻/电位器   阻值 10kΩ   精度 ±25%   额定电压 -   功率 150mW   温度系数 ±250ppm/℃   圈数 1")
      (fields (field (name "MANUFACTURER") "BOURNS") (field (name "MANUFACTURER PART") "TC33X-2-103E"))
      (libsource (lib "SchLib") (part "R10k_KT"))
    )
    (comp (ref "R31")
      (value "1MΩ")
      (footprint "R0603")
      (description "0603电阻")
      (fields
        (field (name "MANUFACTURER") "UNI-ROYAL(厚声)")
        (field (name "MANUFACTURER PART") "0603WAF5100T5E")
      )
      (libsource (lib "SchLib") (part "R0603_1MΩ"))
    )
    (comp (ref "R32")
      (value "1MΩ")
      (footprint "R0603")
      (description "0603电阻")
      (fields
        (field (name "MANUFACTURER") "UNI-ROYAL(厚声)")
        (field (name "MANUFACTURER PART") "0603WAF5100T5E")
      )
      (libsource (lib "SchLib") (part "R0603_1MΩ"))
    )
    (comp (ref "R33")
      (value "200mΩ")
      (footprint "R1206_200mΩ")
      (description "1206电阻")
      (fields
        (field (name "MANUFACTURER") "UNI-ROYAL(厚声)")
        (field (name "MANUFACTURER PART") "1206W4F200LT5E")
      )
      (libsource (lib "SchLib") (part "R1206_200mΩ"))
    )
    (comp (ref "R34")
      (value "200mΩ")
      (footprint "R1206_200mΩ")
      (description "1206电阻")
      (fields
        (field (name "MANUFACTURER") "UNI-ROYAL(厚声)")
        (field (name "MANUFACTURER PART") "1206W4F200LT5E")
      )
      (libsource (lib "SchLib") (part "R1206_200mΩ"))
    )
    (comp (ref "R35")
      (value "200mΩ")
      (footprint "R1206_200mΩ")
      (description "1206电阻")
      (fields
        (field (name "MANUFACTURER") "UNI-ROYAL(厚声)")
        (field (name "MANUFACTURER PART") "1206W4F200LT5E")
      )
      (libsource (lib "SchLib") (part "R1206_200mΩ"))
    )
    (comp (ref "R36")
      (value "200mΩ")
      (footprint "R1206_200mΩ")
      (description "1206电阻")
      (fields
        (field (name "MANUFACTURER") "UNI-ROYAL(厚声)")
        (field (name "MANUFACTURER PART") "1206W4F200LT5E")
      )
      (libsource (lib "SchLib") (part "R1206_200mΩ"))
    )
    (comp (ref "R37")
      (value "10kΩ")
      (footprint "R0603_10KΩ")
      (description "0603电阻")
      (fields
        (field (name "MANUFACTURER") "UNI-ROYAL(厚声)")
        (field (name "MANUFACTURER PART") "0603WAF1002T5E")
      )
      (libsource (lib "SchLib") (part "R0603_10KΩ"))
    )
    (comp (ref "R38")
      (value "10kΩ")
      (footprint "R0603_10KΩ")
      (description "0603电阻")
      (fields
        (field (name "MANUFACTURER") "UNI-ROYAL(厚声)")
        (field (name "MANUFACTURER PART") "0603WAF1002T5E")
      )
      (libsource (lib "SchLib") (part "R0603_10KΩ"))
    )
    (comp (ref "R39")
      (value "10kΩ")
      (footprint "R10k_KT")
      (description "可调电阻/电位器   阻值 10kΩ   精度 ±25%   额定电压 -   功率 150mW   温度系数 ±250ppm/℃   圈数 1")
      (fields (field (name "MANUFACTURER") "BOURNS") (field (name "MANUFACTURER PART") "TC33X-2-103E"))
      (libsource (lib "SchLib") (part "R10k_KT"))
    )
    (comp (ref "R40")
      (value "10kΩ")
      (footprint "R10k_KT")
      (description "可调电阻/电位器   阻值 10kΩ   精度 ±25%   额定电压 -   功率 150mW   温度系数 ±250ppm/℃   圈数 1")
      (fields (field (name "MANUFACTURER") "BOURNS") (field (name "MANUFACTURER PART") "TC33X-2-103E"))
      (libsource (lib "SchLib") (part "R10k_KT"))
    )
    (comp (ref "U1")
      (value "DRV8825PWPR")
      (footprint "DRV8825PWPR")
      (description "步进电机驱动芯片")
      (fields (field (name "MANUFACTURER") "TI(德州仪器)"))
      (libsource (lib "SchLib") (part "DRV8825PWPR"))
    )
    (comp (ref "U2")
      (value "DRV8825PWPR")
      (footprint "DRV8825PWPR")
      (description "步进电机驱动芯片")
      (fields (field (name "MANUFACTURER") "TI(德州仪器)"))
      (libsource (lib "SchLib") (part "DRV8825PWPR"))
    )
    (comp (ref "U3")
      (value "DRV8825PWPR")
      (footprint "DRV8825PWPR")
      (description "步进电机驱动芯片")
      (fields (field (name "MANUFACTURER") "TI(德州仪器)"))
      (libsource (lib "SchLib") (part "DRV8825PWPR"))
    )
    (comp (ref "U4")
      (value "DRV8825PWPR")
      (footprint "DRV8825PWPR")
      (description "步进电机驱动芯片")
      (fields (field (name "MANUFACTURER") "TI(德州仪器)"))
      (libsource (lib "SchLib") (part "DRV8825PWPR"))
    )
    (comp (ref "U5")
      (value "DRV8825PWPR")
      (footprint "DRV8825PWPR")
      (description "步进电机驱动芯片")
      (fields (field (name "MANUFACTURER") "TI(德州仪器)"))
      (libsource (lib "SchLib") (part "DRV8825PWPR"))
    )
    (comp (ref "U6")
      (value "DRV8825PWPR")
      (footprint "DRV8825PWPR")
      (description "步进电机驱动芯片")
      (fields (field (name "MANUFACTURER") "TI(德州仪器)"))
      (libsource (lib "SchLib") (part "DRV8825PWPR"))
    )
    (comp (ref "U7")
      (value "DRV8825PWPR")
      (footprint "DRV8825PWPR")
      (description "步进电机驱动芯片")
      (fields (field (name "MANUFACTURER") "TI(德州仪器)"))
      (libsource (lib "SchLib") (part "DRV8825PWPR"))
    )
    (comp (ref "U8")
      (value "DRV8825PWPR")
      (footprint "DRV8825PWPR")
      (description "步进电机驱动芯片")
      (fields (field (name "MANUFACTURER") "TI(德州仪器)"))
      (libsource (lib "SchLib") (part "DRV8825PWPR"))
    )
  )
  (nets
    (net (code "1") (name "/FAULT1") (class "Default")
      (node (ref "R10") (pin "1") (pinfunction "1_1") (pintype "passive"))
      (node (ref "U1") (pin "18") (pinfunction "nFAULT_18") (pintype "passive"))
    )
    (net (code "2") (name "/FAULT2") (class "Default")
      (node (ref "R11") (pin "1") (pinfunction "1_1") (pintype "passive"))
      (node (ref "U2") (pin "18") (pinfunction "nFAULT_18") (pintype "passive"))
    )
    (net (code "3") (name "/FAULT3") (class "Default")
      (node (ref "R12") (pin "1") (pinfunction "1_1") (pintype "passive"))
      (node (ref "U3") (pin "18") (pinfunction "nFAULT_18") (pintype "passive"))
    )
    (net (code "4") (name "/FAULT4") (class "Default")
      (node (ref "R25") (pin "1") (pinfunction "1_1") (pintype "passive"))
      (node (ref "U4") (pin "18") (pinfunction "nFAULT_18") (pintype "passive"))
    )
    (net (code "5") (name "/FAULT5") (class "Default")
      (node (ref "R26") (pin "1") (pinfunction "1_1") (pintype "passive"))
      (node (ref "U5") (pin "18") (pinfunction "nFAULT_18") (pintype "passive"))
    )
    (net (code "6") (name "/FAULT6") (class "Default")
      (node (ref "R27") (pin "1") (pinfunction "1_1") (pintype "passive"))
      (node (ref "U6") (pin "18") (pinfunction "nFAULT_18") (pintype "passive"))
    )
    (net (code "7") (name "/FAULT7") (class "Default")
      (node (ref "R37") (pin "1") (pinfunction "1_1") (pintype "passive"))
      (node (ref "U7") (pin "18") (pinfunction "nFAULT_18") (pintype "passive"))
    )
    (net (code "8") (name "/FAULT8") (class "Default")
      (node (ref "R38") (pin "1") (pinfunction "1_1") (pintype "passive"))
      (node (ref "U8") (pin "18") (pinfunction "nFAULT_18") (pintype "passive"))
    )
    (net (code "9") (name "/M1A1") (class "Default")
      (node (ref "CN3") (pin "4") (pinfunction "4_4") (pintype "passive"))
      (node (ref "U1") (pin "5") (pinfunction "AOUT1_5") (pintype "passive"))
    )
    (net (code "10") (name "/M1A2") (class "Default")
      (node (ref "CN3") (pin "3") (pinfunction "3_3") (pintype "passive"))
      (node (ref "U1") (pin "7") (pinfunction "AOUT2_7") (pintype "passive"))
    )
    (net (code "11") (name "/M1B1") (class "Default")
      (node (ref "CN3") (pin "1") (pinfunction "1_1") (pintype "passive"))
      (node (ref "U1") (pin "10") (pinfunction "BOUT1_10") (pintype "passive"))
    )
    (net (code "12") (name "/M1B2") (class "Default")
      (node (ref "CN3") (pin "2") (pinfunction "2_2") (pintype "passive"))
      (node (ref "U1") (pin "8") (pinfunction "BOUT2_8") (pintype "passive"))
    )
    (net (code "13") (name "/M1D") (class "Default")
      (node (ref "U1") (pin "20") (pinfunction "DIR_20") (pintype "passive"))
    )
    (net (code "14") (name "/M1SL") (class "Default")
      (node (ref "U1") (pin "16") (pinfunction "nRESET_16") (pintype "passive"))
      (node (ref "U1") (pin "17") (pinfunction "nSLEEP_17") (pintype "passive"))
    )
    (net (code "15") (name "/M1ST") (class "Default")
      (node (ref "U1") (pin "22") (pinfunction "STEP_22") (pintype "passive"))
    )
    (net (code "16") (name "/M2A1") (class "Default")
      (node (ref "CN1") (pin "4") (pinfunction "4_4") (pintype "passive"))
      (node (ref "U2") (pin "5") (pinfunction "AOUT1_5") (pintype "passive"))
    )
    (net (code "17") (name "/M2A2") (class "Default")
      (node (ref "CN1") (pin "3") (pinfunction "3_3") (pintype "passive"))
      (node (ref "U2") (pin "7") (pinfunction "AOUT2_7") (pintype "passive"))
    )
    (net (code "18") (name "/M2B1") (class "Default")
      (node (ref "CN1") (pin "1") (pinfunction "1_1") (pintype "passive"))
      (node (ref "U2") (pin "10") (pinfunction "BOUT1_10") (pintype "passive"))
    )
    (net (code "19") (name "/M2B2") (class "Default")
      (node (ref "CN1") (pin "2") (pinfunction "2_2") (pintype "passive"))
      (node (ref "U2") (pin "8") (pinfunction "BOUT2_8") (pintype "passive"))
    )
    (net (code "20") (name "/M2D") (class "Default")
      (node (ref "U2") (pin "20") (pinfunction "DIR_20") (pintype "passive"))
    )
    (net (code "21") (name "/M2SL") (class "Default")
      (node (ref "U2") (pin "16") (pinfunction "nRESET_16") (pintype "passive"))
      (node (ref "U2") (pin "17") (pinfunction "nSLEEP_17") (pintype "passive"))
    )
    (net (code "22") (name "/M2ST") (class "Default")
      (node (ref "U2") (pin "22") (pinfunction "STEP_22") (pintype "passive"))
    )
    (net (code "23") (name "/M3A1") (class "Default")
      (node (ref "CN2") (pin "4") (pinfunction "4_4") (pintype "passive"))
      (node (ref "U3") (pin "5") (pinfunction "AOUT1_5") (pintype "passive"))
    )
    (net (code "24") (name "/M3A2") (class "Default")
      (node (ref "CN2") (pin "3") (pinfunction "3_3") (pintype "passive"))
      (node (ref "U3") (pin "7") (pinfunction "AOUT2_7") (pintype "passive"))
    )
    (net (code "25") (name "/M3B1") (class "Default")
      (node (ref "CN2") (pin "1") (pinfunction "1_1") (pintype "passive"))
      (node (ref "U3") (pin "10") (pinfunction "BOUT1_10") (pintype "passive"))
    )
    (net (code "26") (name "/M3B2") (class "Default")
      (node (ref "CN2") (pin "2") (pinfunction "2_2") (pintype "passive"))
      (node (ref "U3") (pin "8") (pinfunction "BOUT2_8") (pintype "passive"))
    )
    (net (code "27") (name "/M3D") (class "Default")
      (node (ref "U3") (pin "20") (pinfunction "DIR_20") (pintype "passive"))
    )
    (net (code "28") (name "/M3SL") (class "Default")
      (node (ref "U3") (pin "16") (pinfunction "nRESET_16") (pintype "passive"))
      (node (ref "U3") (pin "17") (pinfunction "nSLEEP_17") (pintype "passive"))
    )
    (net (code "29") (name "/M3ST") (class "Default")
      (node (ref "U3") (pin "22") (pinfunction "STEP_22") (pintype "passive"))
    )
    (net (code "30") (name "/M4A1") (class "Default")
      (node (ref "CN4") (pin "4") (pinfunction "4_4") (pintype "passive"))
      (node (ref "U4") (pin "5") (pinfunction "AOUT1_5") (pintype "passive"))
    )
    (net (code "31") (name "/M4A2") (class "Default")
      (node (ref "CN4") (pin "3") (pinfunction "3_3") (pintype "passive"))
      (node (ref "U4") (pin "7") (pinfunction "AOUT2_7") (pintype "passive"))
    )
    (net (code "32") (name "/M4B1") (class "Default")
      (node (ref "CN4") (pin "1") (pinfunction "1_1") (pintype "passive"))
      (node (ref "U4") (pin "10") (pinfunction "BOUT1_10") (pintype "passive"))
    )
    (net (code "33") (name "/M4B2") (class "Default")
      (node (ref "CN4") (pin "2") (pinfunction "2_2") (pintype "passive"))
      (node (ref "U4") (pin "8") (pinfunction "BOUT2_8") (pintype "passive"))
    )
    (net (code "34") (name "/M4D") (class "Default")
      (node (ref "U4") (pin "20") (pinfunction "DIR_20") (pintype "passive"))
    )
    (net (code "35") (name "/M4SL") (class "Default")
      (node (ref "U4") (pin "16") (pinfunction "nRESET_16") (pintype "passive"))
      (node (ref "U4") (pin "17") (pinfunction "nSLEEP_17") (pintype "passive"))
    )
    (net (code "36") (name "/M4ST") (class "Default")
      (node (ref "U4") (pin "22") (pinfunction "STEP_22") (pintype "passive"))
    )
    (net (code "37") (name "/M5A1") (class "Default")
      (node (ref "CN5") (pin "4") (pinfunction "4_4") (pintype "passive"))
      (node (ref "U5") (pin "5") (pinfunction "AOUT1_5") (pintype "passive"))
    )
    (net (code "38") (name "/M5A2") (class "Default")
      (node (ref "CN5") (pin "3") (pinfunction "3_3") (pintype "passive"))
      (node (ref "U5") (pin "7") (pinfunction "AOUT2_7") (pintype "passive"))
    )
    (net (code "39") (name "/M5B1") (class "Default")
      (node (ref "CN5") (pin "1") (pinfunction "1_1") (pintype "passive"))
      (node (ref "U5") (pin "10") (pinfunction "BOUT1_10") (pintype "passive"))
    )
    (net (code "40") (name "/M5B2") (class "Default")
      (node (ref "CN5") (pin "2") (pinfunction "2_2") (pintype "passive"))
      (node (ref "U5") (pin "8") (pinfunction "BOUT2_8") (pintype "passive"))
    )
    (net (code "41") (name "/M5D") (class "Default")
      (node (ref "U5") (pin "20") (pinfunction "DIR_20") (pintype "passive"))
    )
    (net (code "42") (name "/M5SL") (class "Default")
      (node (ref "U5") (pin "16") (pinfunction "nRESET_16") (pintype "passive"))
      (node (ref "U5") (pin "17") (pinfunction "nSLEEP_17") (pintype "passive"))
    )
    (net (code "43") (name "/M5ST") (class "Default")
      (node (ref "U5") (pin "22") (pinfunction "STEP_22") (pintype "passive"))
    )
    (net (code "44") (name "/M6A1") (class "Default")
      (node (ref "CN6") (pin "4") (pinfunction "4_4") (pintype "passive"))
      (node (ref "U6") (pin "5") (pinfunction "AOUT1_5") (pintype "passive"))
    )
    (net (code "45") (name "/M6A2") (class "Default")
      (node (ref "CN6") (pin "3") (pinfunction "3_3") (pintype "passive"))
      (node (ref "U6") (pin "7") (pinfunction "AOUT2_7") (pintype "passive"))
    )
    (net (code "46") (name "/M6B1") (class "Default")
      (node (ref "CN6") (pin "1") (pinfunction "1_1") (pintype "passive"))
      (node (ref "U6") (pin "10") (pinfunction "BOUT1_10") (pintype "passive"))
    )
    (net (code "47") (name "/M6B2") (class "Default")
      (node (ref "CN6") (pin "2") (pinfunction "2_2") (pintype "passive"))
      (node (ref "U6") (pin "8") (pinfunction "BOUT2_8") (pintype "passive"))
    )
    (net (code "48") (name "/M6D") (class "Default")
      (node (ref "U6") (pin "20") (pinfunction "DIR_20") (pintype "passive"))
    )
    (net (code "49") (name "/M6SL") (class "Default")
      (node (ref "U6") (pin "16") (pinfunction "nRESET_16") (pintype "passive"))
      (node (ref "U6") (pin "17") (pinfunction "nSLEEP_17") (pintype "passive"))
    )
    (net (code "50") (name "/M6ST") (class "Default")
      (node (ref "U6") (pin "22") (pinfunction "STEP_22") (pintype "passive"))
    )
    (net (code "51") (name "/M7A1") (class "Default")
      (node (ref "CN7") (pin "4") (pinfunction "4_4") (pintype "passive"))
      (node (ref "U7") (pin "5") (pinfunction "AOUT1_5") (pintype "passive"))
    )
    (net (code "52") (name "/M7A2") (class "Default")
      (node (ref "CN7") (pin "3") (pinfunction "3_3") (pintype "passive"))
      (node (ref "U7") (pin "7") (pinfunction "AOUT2_7") (pintype "passive"))
    )
    (net (code "53") (name "/M7B1") (class "Default")
      (node (ref "CN7") (pin "1") (pinfunction "1_1") (pintype "passive"))
      (node (ref "U7") (pin "10") (pinfunction "BOUT1_10") (pintype "passive"))
    )
    (net (code "54") (name "/M7B2") (class "Default")
      (node (ref "CN7") (pin "2") (pinfunction "2_2") (pintype "passive"))
      (node (ref "U7") (pin "8") (pinfunction "BOUT2_8") (pintype "passive"))
    )
    (net (code "55") (name "/M7D") (class "Default")
      (node (ref "U7") (pin "20") (pinfunction "DIR_20") (pintype "passive"))
    )
    (net (code "56") (name "/M7SL") (class "Default")
      (node (ref "U7") (pin "16") (pinfunction "nRESET_16") (pintype "passive"))
      (node (ref "U7") (pin "17") (pinfunction "nSLEEP_17") (pintype "passive"))
    )
    (net (code "57") (name "/M7ST") (class "Default")
      (node (ref "U7") (pin "22") (pinfunction "STEP_22") (pintype "passive"))
    )
    (net (code "58") (name "/M8A1") (class "Default")
      (node (ref "CN8") (pin "4") (pinfunction "4_4") (pintype "passive"))
      (node (ref "U8") (pin "5") (pinfunction "AOUT1_5") (pintype "passive"))
    )
    (net (code "59") (name "/M8A2") (class "Default")
      (node (ref "CN8") (pin "3") (pinfunction "3_3") (pintype "passive"))
      (node (ref "U8") (pin "7") (pinfunction "AOUT2_7") (pintype "passive"))
    )
    (net (code "60") (name "/M8B1") (class "Default")
      (node (ref "CN8") (pin "1") (pinfunction "1_1") (pintype "passive"))
      (node (ref "U8") (pin "10") (pinfunction "BOUT1_10") (pintype "passive"))
    )
    (net (code "61") (name "/M8B2") (class "Default")
      (node (ref "CN8") (pin "2") (pinfunction "2_2") (pintype "passive"))
      (node (ref "U8") (pin "8") (pinfunction "BOUT2_8") (pintype "passive"))
    )
    (net (code "62") (name "/M8D") (class "Default")
      (node (ref "U8") (pin "20") (pinfunction "DIR_20") (pintype "passive"))
    )
    (net (code "63") (name "/M8SL") (class "Default")
      (node (ref "U8") (pin "16") (pinfunction "nRESET_16") (pintype "passive"))
      (node (ref "U8") (pin "17") (pinfunction "nSLEEP_17") (pintype "passive"))
    )
    (net (code "64") (name "/M8ST") (class "Default")
      (node (ref "U8") (pin "22") (pinfunction "STEP_22") (pintype "passive"))
    )
    (net (code "65") (name "/MCU_Vref") (class "Default")
      (node (ref "H1") (pin "3") (pinfunction "3_3") (pintype "passive"))
      (node (ref "H2") (pin "3") (pinfunction "3_3") (pintype "passive"))
      (node (ref "H3") (pin "3") (pinfunction "3_3") (pintype "passive"))
      (node (ref "H4") (pin "3") (pinfunction "3_3") (pintype "passive"))
      (node (ref "H5") (pin "3") (pinfunction "3_3") (pintype "passive"))
      (node (ref "H6") (pin "3") (pinfunction "3_3") (pintype "passive"))
      (node (ref "H7") (pin "3") (pinfunction "3_3") (pintype "passive"))
      (node (ref "H8") (pin "3") (pinfunction "3_3") (pintype "passive"))
    )
    (net (code "66") (name "/NEN") (class "Default")
      (node (ref "U1") (pin "21") (pinfunction "NENBL_21") (pintype "passive"))
      (node (ref "U2") (pin "21") (pinfunction "NENBL_21") (pintype "passive"))
      (node (ref "U3") (pin "21") (pinfunction "NENBL_21") (pintype "passive"))
      (node (ref "U4") (pin "21") (pinfunction "NENBL_21") (pintype "passive"))
      (node (ref "U5") (pin "21") (pinfunction "NENBL_21") (pintype "passive"))
      (node (ref "U6") (pin "21") (pinfunction "NENBL_21") (pintype "passive"))
      (node (ref "U7") (pin "21") (pinfunction "NENBL_21") (pintype "passive"))
      (node (ref "U8") (pin "21") (pinfunction "NENBL_21") (pintype "passive"))
    )
    (net (code "67") (name "/R_Vref1") (class "Default")
      (node (ref "H1") (pin "1") (pinfunction "1_1") (pintype "passive"))
      (node (ref "R13") (pin "2") (pinfunction "2_2") (pintype "passive"))
    )
    (net (code "68") (name "/R_Vref2") (class "Default")
      (node (ref "H2") (pin "1") (pinfunction "1_1") (pintype "passive"))
      (node (ref "R14") (pin "2") (pinfunction "2_2") (pintype "passive"))
    )
    (net (code "69") (name "/R_Vref3") (class "Default")
      (node (ref "H3") (pin "1") (pinfunction "1_1") (pintype "passive"))
      (node (ref "R15") (pin "2") (pinfunction "2_2") (pintype "passive"))
    )
    (net (code "70") (name "/R_Vref4") (class "Default")
      (node (ref "H4") (pin "1") (pinfunction "1_1") (pintype "passive"))
      (node (ref "R28") (pin "2") (pinfunction "2_2") (pintype "passive"))
    )
    (net (code "71") (name "/R_Vref5") (class "Default")
      (node (ref "H5") (pin "1") (pinfunction "1_1") (pintype "passive"))
      (node (ref "R29") (pin "2") (pinfunction "2_2") (pintype "passive"))
    )
    (net (code "72") (name "/R_Vref6") (class "Default")
      (node (ref "H6") (pin "1") (pinfunction "1_1") (pintype "passive"))
      (node (ref "R30") (pin "2") (pinfunction "2_2") (pintype "passive"))
    )
    (net (code "73") (name "/R_Vref7") (class "Default")
      (node (ref "H7") (pin "1") (pinfunction "1_1") (pintype "passive"))
      (node (ref "R39") (pin "2") (pinfunction "2_2") (pintype "passive"))
    )
    (net (code "74") (name "/R_Vref8") (class "Default")
      (node (ref "H8") (pin "1") (pinfunction "1_1") (pintype "passive"))
      (node (ref "R40") (pin "2") (pinfunction "2_2") (pintype "passive"))
    )
    (net (code "75") (name "/Vref1") (class "Default")
      (node (ref "H1") (pin "2") (pinfunction "2_2") (pintype "passive"))
      (node (ref "U1") (pin "12") (pinfunction "AVREF_12") (pintype "passive"))
      (node (ref "U1") (pin "13") (pinfunction "BVREF_13") (pintype "passive"))
    )
    (net (code "76") (name "/Vref2") (class "Default")
      (node (ref "H2") (pin "2") (pinfunction "2_2") (pintype "passive"))
      (node (ref "U2") (pin "12") (pinfunction "AVREF_12") (pintype "passive"))
      (node (ref "U2") (pin "13") (pinfunction "BVREF_13") (pintype "passive"))
    )
    (net (code "77") (name "/Vref3") (class "Default")
      (node (ref "H3") (pin "2") (pinfunction "2_2") (pintype "passive"))
      (node (ref "U3") (pin "12") (pinfunction "AVREF_12") (pintype "passive"))
      (node (ref "U3") (pin "13") (pinfunction "BVREF_13") (pintype "passive"))
    )
    (net (code "78") (name "/Vref4") (class "Default")
      (node (ref "H4") (pin "2") (pinfunction "2_2") (pintype "passive"))
      (node (ref "U4") (pin "12") (pinfunction "AVREF_12") (pintype "passive"))
      (node (ref "U4") (pin "13") (pinfunction "BVREF_13") (pintype "passive"))
    )
    (net (code "79") (name "/Vref5") (class "Default")
      (node (ref "H5") (pin "2") (pinfunction "2_2") (pintype "passive"))
      (node (ref "U5") (pin "12") (pinfunction "AVREF_12") (pintype "passive"))
      (node (ref "U5") (pin "13") (pinfunction "BVREF_13") (pintype "passive"))
    )
    (net (code "80") (name "/Vref6") (class "Default")
      (node (ref "H6") (pin "2") (pinfunction "2_2") (pintype "passive"))
      (node (ref "U6") (pin "12") (pinfunction "AVREF_12") (pintype "passive"))
      (node (ref "U6") (pin "13") (pinfunction "BVREF_13") (pintype "passive"))
    )
    (net (code "81") (name "/Vref7") (class "Default")
      (node (ref "H7") (pin "2") (pinfunction "2_2") (pintype "passive"))
      (node (ref "U7") (pin "12") (pinfunction "AVREF_12") (pintype "passive"))
      (node (ref "U7") (pin "13") (pinfunction "BVREF_13") (pintype "passive"))
    )
    (net (code "82") (name "/Vref8") (class "Default")
      (node (ref "H8") (pin "2") (pinfunction "2_2") (pintype "passive"))
      (node (ref "U8") (pin "12") (pinfunction "AVREF_12") (pintype "passive"))
      (node (ref "U8") (pin "13") (pinfunction "BVREF_13") (pintype "passive"))
    )
    (net (code "83") (name "GND") (class "Default")
      (node (ref "C10") (pin "2") (pinfunction "2_2") (pintype "passive"))
      (node (ref "C11") (pin "2") (pinfunction "2_2") (pintype "passive"))
      (node (ref "C12") (pin "2") (pinfunction "2_2") (pintype "passive"))
      (node (ref "C13") (pin "1") (pinfunction "1_1") (pintype "passive"))
      (node (ref "C14") (pin "1") (pinfunction "1_1") (pintype "passive"))
      (node (ref "C15") (pin "1") (pinfunction "1_1") (pintype "passive"))
      (node (ref "C16") (pin "1") (pinfunction "1_1") (pintype "passive"))
      (node (ref "C17") (pin "1") (pinfunction "1_1") (pintype "passive"))
      (node (ref "C18") (pin "1") (pinfunction "1_1") (pintype "passive"))
      (node (ref "C25") (pin "1") (pinfunction "1_1") (pintype "passive"))
      (node (ref "C26") (pin "1") (pinfunction "1_1") (pintype "passive"))
      (node (ref "C27") (pin "1") (pinfunction "1_1") (pintype "passive"))
      (node (ref "C28") (pin "2") (pinfunction "2_2") (pintype "passive"))
      (node (ref "C29") (pin "2") (pinfunction "2_2") (pintype "passive"))
      (node (ref "C30") (pin "2") (pinfunction "2_2") (pintype "passive"))
      (node (ref "C31") (pin "1") (pinfunction "1_1") (pintype "passive"))
      (node (ref "C32") (pin "1") (pinfunction "1_1") (pintype "passive"))
      (node (ref "C33") (pin "1") (pinfunction "1_1") (pintype "passive"))
      (node (ref "C34") (pin "1") (pinfunction "1_1") (pintype "passive"))
      (node (ref "C35") (pin "1") (pinfunction "1_1") (pintype "passive"))
      (node (ref "C36") (pin "1") (pinfunction "1_1") (pintype "passive"))
      (node (ref "C41") (pin "1") (pinfunction "1_1") (pintype "passive"))
      (node (ref "C42") (pin "1") (pinfunction "1_1") (pintype "passive"))
      (node (ref "C43") (pin "2") (pinfunction "2_2") (pintype "passive"))
      (node (ref "C44") (pin "2") (pinfunction "2_2") (pintype "passive"))
      (node (ref "C45") (pin "1") (pinfunction "1_1") (pintype "passive"))
      (node (ref "C46") (pin "1") (pinfunction "1_1") (pintype "passive"))
      (node (ref "C47") (pin "1") (pinfunction "1_1") (pintype "passive"))
      (node (ref "C48") (pin "1") (pinfunction "1_1") (pintype "passive"))
      (node (ref "C7") (pin "1") (pinfunction "1_1") (pintype "passive"))
      (node (ref "C8") (pin "1") (pinfunction "1_1") (pintype "passive"))
      (node (ref "C9") (pin "1") (pinfunction "1_1") (pintype "passive"))
      (node (ref "R13") (pin "1") (pinfunction "1_1") (pintype "passive"))
      (node (ref "R14") (pin "1") (pinfunction "1_1") (pintype "passive"))
      (node (ref "R15") (pin "1") (pinfunction "1_1") (pintype "passive"))
      (node (ref "R19") (pin "1") (pinfunction "1_1") (pintype "passive"))
      (node (ref "R20") (pin "1") (pinfunction "1_1") (pintype "passive"))
      (node (ref "R21") (pin "1") (pinfunction "1_1") (pintype "passive"))
      (node (ref "R22") (pin "1") (pinfunction "1_1") (pintype "passive"))
      (node (ref "R23") (pin "1") (pinfunction "1_1") (pintype "passive"))
      (node (ref "R24") (pin "1") (pinfunction "1_1") (pintype "passive"))
      (node (ref "R28") (pin "1") (pinfunction "1_1") (pintype "passive"))
      (node (ref "R29") (pin "1") (pinfunction "1_1") (pintype "passive"))
      (node (ref "R30") (pin "1") (pinfunction "1_1") (pintype "passive"))
      (node (ref "R33") (pin "1") (pinfunction "1_1") (pintype "passive"))
      (node (ref "R34") (pin "1") (pinfunction "1_1") (pintype "passive"))
      (node (ref "R35") (pin "1") (pinfunction "1_1") (pintype "passive"))
      (node (ref "R36") (pin "1") (pinfunction "1_1") (pintype "passive"))
      (node (ref "R39") (pin "1") (pinfunction "1_1") (pintype "passive"))
      (node (ref "R4") (pin "1") (pinfunction "1_1") (pintype "passive"))
      (node (ref "R40") (pin "1") (pinfunction "1_1") (pintype "passive"))
      (node (ref "R5") (pin "1") (pinfunction "1_1") (pintype "passive"))
      (node (ref "R6") (pin "1") (pinfunction "1_1") (pintype "passive"))
      (node (ref "R7") (pin "1") (pinfunction "1_1") (pintype "passive"))
      (node (ref "R8") (pin "1") (pinfunction "1_1") (pintype "passive"))
      (node (ref "R9") (pin "1") (pinfunction "1_1") (pintype "passive"))
      (node (ref "U1") (pin "14") (pinfunction "GND_14") (pintype "passive"))
      (node (ref "U1") (pin "24") (pinfunction "MODE0_24") (pintype "passive"))
      (node (ref "U1") (pin "25") (pinfunction "MODE1_25") (pintype "passive"))
      (node (ref "U1") (pin "26") (pinfunction "MODE2_26") (pintype "passive"))
      (node (ref "U1") (pin "28") (pinfunction "GND_28") (pintype "passive"))
      (node (ref "U1") (pin "29") (pinfunction "EP_29") (pintype "passive"))
      (node (ref "U2") (pin "14") (pinfunction "GND_14") (pintype "passive"))
      (node (ref "U2") (pin "24") (pinfunction "MODE0_24") (pintype "passive"))
      (node (ref "U2") (pin "25") (pinfunction "MODE1_25") (pintype "passive"))
      (node (ref "U2") (pin "26") (pinfunction "MODE2_26") (pintype "passive"))
      (node (ref "U2") (pin "28") (pinfunction "GND_28") (pintype "passive"))
      (node (ref "U2") (pin "29") (pinfunction "EP_29") (pintype "passive"))
      (node (ref "U3") (pin "14") (pinfunction "GND_14") (pintype "passive"))
      (node (ref "U3") (pin "24") (pinfunction "MODE0_24") (pintype "passive"))
      (node (ref "U3") (pin "25") (pinfunction "MODE1_25") (pintype "passive"))
      (node (ref "U3") (pin "26") (pinfunction "MODE2_26") (pintype "passive"))
      (node (ref "U3") (pin "28") (pinfunction "GND_28") (pintype "passive"))
      (node (ref "U3") (pin "29") (pinfunction "EP_29") (pintype "passive"))
      (node (ref "U4") (pin "14") (pinfunction "GND_14") (pintype "passive"))
      (node (ref "U4") (pin "24") (pinfunction "MODE0_24") (pintype "passive"))
      (node (ref "U4") (pin "25") (pinfunction "MODE1_25") (pintype "passive"))
      (node (ref "U4") (pin "26") (pinfunction "MODE2_26") (pintype "passive"))
      (node (ref "U4") (pin "28") (pinfunction "GND_28") (pintype "passive"))
      (node (ref "U4") (pin "29") (pinfunction "EP_29") (pintype "passive"))
      (node (ref "U5") (pin "14") (pinfunction "GND_14") (pintype "passive"))
      (node (ref "U5") (pin "24") (pinfunction "MODE0_24") (pintype "passive"))
      (node (ref "U5") (pin "25") (pinfunction "MODE1_25") (pintype "passive"))
      (node (ref "U5") (pin "26") (pinfunction "MODE2_26") (pintype "passive"))
      (node (ref "U5") (pin "28") (pinfunction "GND_28") (pintype "passive"))
      (node (ref "U5") (pin "29") (pinfunction "EP_29") (pintype "passive"))
      (node (ref "U6") (pin "14") (pinfunction "GND_14") (pintype "passive"))
      (node (ref "U6") (pin "24") (pinfunction "MODE0_24") (pintype "passive"))
      (node (ref "U6") (pin "25") (pinfunction "MODE1_25") (pintype "passive"))
      (node (ref "U6") (pin "26") (pinfunction "MODE2_26") (pintype "passive"))
      (node (ref "U6") (pin "28") (pinfunction "GND_28") (pintype "passive"))
      (node (ref "U6") (pin "29") (pinfunction "EP_29") (pintype "passive"))
      (node (ref "U7") (pin "14") (pinfunction "GND_14") (pintype "passive"))
      (node (ref "U7") (pin "24") (pinfunction "MODE0_24") (pintype "passive"))
      (node (ref "U7") (pin "25") (pinfunction "MODE1_25") (pintype "passive"))
      (node (ref "U7") (pin "26") (pinfunction "MODE2_26") (pintype "passive"))
      (node (ref "U7") (pin "28") (pinfunction "GND_28") (pintype "passive"))
      (node (ref "U7") (pin "29") (pinfunction "EP_29") (pintype "passive"))
      (node (ref "U8") (pin "14") (pinfunction "GND_14") (pintype "passive"))
      (node (ref "U8") (pin "24") (pinfunction "MODE0_24") (pintype "passive"))
      (node (ref "U8") (pin "25") (pinfunction "MODE1_25") (pintype "passive"))
      (node (ref "U8") (pin "26") (pinfunction "MODE2_26") (pintype "passive"))
      (node (ref "U8") (pin "28") (pinfunction "GND_28") (pintype "passive"))
      (node (ref "U8") (pin "29") (pinfunction "EP_29") (pintype "passive"))
    )
    (net (code "84") (name "Net-(U1-CP1)") (class "Default")
      (node (ref "C1") (pin "2") (pinfunction "2_2") (pintype "passive"))
      (node (ref "U1") (pin "1") (pinfunction "CP1_1") (pintype "passive"))
    )
    (net (code "85") (name "Net-(U1-CP2)") (class "Default")
      (node (ref "C1") (pin "1") (pinfunction "1_1") (pintype "passive"))
      (node (ref "U1") (pin "2") (pinfunction "CP2_2") (pintype "passive"))
    )
    (net (code "86") (name "Net-(U1-ISENA)") (class "Default")
      (node (ref "R4") (pin "2") (pinfunction "2_2") (pintype "passive"))
      (node (ref "U1") (pin "6") (pinfunction "ISENA_6") (pintype "passive"))
    )
    (net (code "87") (name "Net-(U1-ISENB)") (class "Default")
      (node (ref "R7") (pin "2") (pinfunction "2_2") (pintype "passive"))
      (node (ref "U1") (pin "9") (pinfunction "ISENB_9") (pintype "passive"))
    )
    (net (code "88") (name "Net-(U1-VCP)") (class "Default")
      (node (ref "C4") (pin "1") (pinfunction "1_1") (pintype "passive"))
      (node (ref "R3") (pin "2") (pinfunction "2_2") (pintype "passive"))
      (node (ref "U1") (pin "3") (pinfunction "VCP_3") (pintype "passive"))
    )
    (net (code "89") (name "Net-(U2-CP1)") (class "Default")
      (node (ref "C2") (pin "2") (pinfunction "2_2") (pintype "passive"))
      (node (ref "U2") (pin "1") (pinfunction "CP1_1") (pintype "passive"))
    )
    (net (code "90") (name "Net-(U2-CP2)") (class "Default")
      (node (ref "C2") (pin "1") (pinfunction "1_1") (pintype "passive"))
      (node (ref "U2") (pin "2") (pinfunction "CP2_2") (pintype "passive"))
    )
    (net (code "91") (name "Net-(U2-ISENA)") (class "Default")
      (node (ref "R5") (pin "2") (pinfunction "2_2") (pintype "passive"))
      (node (ref "U2") (pin "6") (pinfunction "ISENA_6") (pintype "passive"))
    )
    (net (code "92") (name "Net-(U2-ISENB)") (class "Default")
      (node (ref "R8") (pin "2") (pinfunction "2_2") (pintype "passive"))
      (node (ref "U2") (pin "9") (pinfunction "ISENB_9") (pintype "passive"))
    )
    (net (code "93") (name "Net-(U2-VCP)") (class "Default")
      (node (ref "C5") (pin "1") (pinfunction "1_1") (pintype "passive"))
      (node (ref "R1") (pin "2") (pinfunction "2_2") (pintype "passive"))
      (node (ref "U2") (pin "3") (pinfunction "VCP_3") (pintype "passive"))
    )
    (net (code "94") (name "Net-(U3-CP1)") (class "Default")
      (node (ref "C3") (pin "2") (pinfunction "2_2") (pintype "passive"))
      (node (ref "U3") (pin "1") (pinfunction "CP1_1") (pintype "passive"))
    )
    (net (code "95") (name "Net-(U3-CP2)") (class "Default")
      (node (ref "C3") (pin "1") (pinfunction "1_1") (pintype "passive"))
      (node (ref "U3") (pin "2") (pinfunction "CP2_2") (pintype "passive"))
    )
    (net (code "96") (name "Net-(U3-ISENA)") (class "Default")
      (node (ref "R6") (pin "2") (pinfunction "2_2") (pintype "passive"))
      (node (ref "U3") (pin "6") (pinfunction "ISENA_6") (pintype "passive"))
    )
    (net (code "97") (name "Net-(U3-ISENB)") (class "Default")
      (node (ref "R9") (pin "2") (pinfunction "2_2") (pintype "passive"))
      (node (ref "U3") (pin "9") (pinfunction "ISENB_9") (pintype "passive"))
    )
    (net (code "98") (name "Net-(U3-VCP)") (class "Default")
      (node (ref "C6") (pin "1") (pinfunction "1_1") (pintype "passive"))
      (node (ref "R2") (pin "2") (pinfunction "2_2") (pintype "passive"))
      (node (ref "U3") (pin "3") (pinfunction "VCP_3") (pintype "passive"))
    )
    (net (code "99") (name "Net-(U4-CP1)") (class "Default")
      (node (ref "C19") (pin "2") (pinfunction "2_2") (pintype "passive"))
      (node (ref "U4") (pin "1") (pinfunction "CP1_1") (pintype "passive"))
    )
    (net (code "100") (name "Net-(U4-CP2)") (class "Default")
      (node (ref "C19") (pin "1") (pinfunction "1_1") (pintype "passive"))
      (node (ref "U4") (pin "2") (pinfunction "CP2_2") (pintype "passive"))
    )
    (net (code "101") (name "Net-(U4-ISENA)") (class "Default")
      (node (ref "R19") (pin "2") (pinfunction "2_2") (pintype "passive"))
      (node (ref "U4") (pin "6") (pinfunction "ISENA_6") (pintype "passive"))
    )
    (net (code "102") (name "Net-(U4-ISENB)") (class "Default")
      (node (ref "R22") (pin "2") (pinfunction "2_2") (pintype "passive"))
      (node (ref "U4") (pin "9") (pinfunction "ISENB_9") (pintype "passive"))
    )
    (net (code "103") (name "Net-(U4-VCP)") (class "Default")
      (node (ref "C22") (pin "1") (pinfunction "1_1") (pintype "passive"))
      (node (ref "R16") (pin "2") (pinfunction "2_2") (pintype "passive"))
      (node (ref "U4") (pin "3") (pinfunction "VCP_3") (pintype "passive"))
    )
    (net (code "104") (name "Net-(U5-CP1)") (class "Default")
      (node (ref "C20") (pin "2") (pinfunction "2_2") (pintype "passive"))
      (node (ref "U5") (pin "1") (pinfunction "CP1_1") (pintype "passive"))
    )
    (net (code "105") (name "Net-(U5-CP2)") (class "Default")
      (node (ref "C20") (pin "1") (pinfunction "1_1") (pintype "passive"))
      (node (ref "U5") (pin "2") (pinfunction "CP2_2") (pintype "passive"))
    )
    (net (code "106") (name "Net-(U5-ISENA)") (class "Default")
      (node (ref "R20") (pin "2") (pinfunction "2_2") (pintype "passive"))
      (node (ref "U5") (pin "6") (pinfunction "ISENA_6") (pintype "passive"))
    )
    (net (code "107") (name "Net-(U5-ISENB)") (class "Default")
      (node (ref "R23") (pin "2") (pinfunction "2_2") (pintype "passive"))
      (node (ref "U5") (pin "9") (pinfunction "ISENB_9") (pintype "passive"))
    )
    (net (code "108") (name "Net-(U5-VCP)") (class "Default")
      (node (ref "C23") (pin "1") (pinfunction "1_1") (pintype "passive"))
      (node (ref "R17") (pin "2") (pinfunction "2_2") (pintype "passive"))
      (node (ref "U5") (pin "3") (pinfunction "VCP_3") (pintype "passive"))
    )
    (net (code "109") (name "Net-(U6-CP1)") (class "Default")
      (node (ref "C21") (pin "2") (pinfunction "2_2") (pintype "passive"))
      (node (ref "U6") (pin "1") (pinfunction "CP1_1") (pintype "passive"))
    )
    (net (code "110") (name "Net-(U6-CP2)") (class "Default")
      (node (ref "C21") (pin "1") (pinfunction "1_1") (pintype "passive"))
      (node (ref "U6") (pin "2") (pinfunction "CP2_2") (pintype "passive"))
    )
    (net (code "111") (name "Net-(U6-ISENA)") (class "Default")
      (node (ref "R21") (pin "2") (pinfunction "2_2") (pintype "passive"))
      (node (ref "U6") (pin "6") (pinfunction "ISENA_6") (pintype "passive"))
    )
    (net (code "112") (name "Net-(U6-ISENB)") (class "Default")
      (node (ref "R24") (pin "2") (pinfunction "2_2") (pintype "passive"))
      (node (ref "U6") (pin "9") (pinfunction "ISENB_9") (pintype "passive"))
    )
    (net (code "113") (name "Net-(U6-VCP)") (class "Default")
      (node (ref "C24") (pin "1") (pinfunction "1_1") (pintype "passive"))
      (node (ref "R18") (pin "2") (pinfunction "2_2") (pintype "passive"))
      (node (ref "U6") (pin "3") (pinfunction "VCP_3") (pintype "passive"))
    )
    (net (code "114") (name "Net-(U7-CP1)") (class "Default")
      (node (ref "C37") (pin "2") (pinfunction "2_2") (pintype "passive"))
      (node (ref "U7") (pin "1") (pinfunction "CP1_1") (pintype "passive"))
    )
    (net (code "115") (name "Net-(U7-CP2)") (class "Default")
      (node (ref "C37") (pin "1") (pinfunction "1_1") (pintype "passive"))
      (node (ref "U7") (pin "2") (pinfunction "CP2_2") (pintype "passive"))
    )
    (net (code "116") (name "Net-(U7-ISENA)") (class "Default")
      (node (ref "R33") (pin "2") (pinfunction "2_2") (pintype "passive"))
      (node (ref "U7") (pin "6") (pinfunction "ISENA_6") (pintype "passive"))
    )
    (net (code "117") (name "Net-(U7-ISENB)") (class "Default")
      (node (ref "R35") (pin "2") (pinfunction "2_2") (pintype "passive"))
      (node (ref "U7") (pin "9") (pinfunction "ISENB_9") (pintype "passive"))
    )
    (net (code "118") (name "Net-(U7-VCP)") (class "Default")
      (node (ref "C39") (pin "1") (pinfunction "1_1") (pintype "passive"))
      (node (ref "R31") (pin "2") (pinfunction "2_2") (pintype "passive"))
      (node (ref "U7") (pin "3") (pinfunction "VCP_3") (pintype "passive"))
    )
    (net (code "119") (name "Net-(U8-CP1)") (class "Default")
      (node (ref "C38") (pin "2") (pinfunction "2_2") (pintype "passive"))
      (node (ref "U8") (pin "1") (pinfunction "CP1_1") (pintype "passive"))
    )
    (net (code "120") (name "Net-(U8-CP2)") (class "Default")
      (node (ref "C38") (pin "1") (pinfunction "1_1") (pintype "passive"))
      (node (ref "U8") (pin "2") (pinfunction "CP2_2") (pintype "passive"))
    )
    (net (code "121") (name "Net-(U8-ISENA)") (class "Default")
      (node (ref "R34") (pin "2") (pinfunction "2_2") (pintype "passive"))
      (node (ref "U8") (pin "6") (pinfunction "ISENA_6") (pintype "passive"))
    )
    (net (code "122") (name "Net-(U8-ISENB)") (class "Default")
      (node (ref "R36") (pin "2") (pinfunction "2_2") (pintype "passive"))
      (node (ref "U8") (pin "9") (pinfunction "ISENB_9") (pintype "passive"))
    )
    (net (code "123") (name "Net-(U8-VCP)") (class "Default")
      (node (ref "C40") (pin "1") (pinfunction "1_1") (pintype "passive"))
      (node (ref "R32") (pin "2") (pinfunction "2_2") (pintype "passive"))
      (node (ref "U8") (pin "3") (pinfunction "VCP_3") (pintype "passive"))
    )
    (net (code "124") (name "VDD") (class "Default")
      (node (ref "C14") (pin "2") (pinfunction "2_2") (pintype "passive"))
      (node (ref "C15") (pin "2") (pinfunction "2_2") (pintype "passive"))
      (node (ref "C16") (pin "2") (pinfunction "2_2") (pintype "passive"))
      (node (ref "C31") (pin "2") (pinfunction "2_2") (pintype "passive"))
      (node (ref "C32") (pin "2") (pinfunction "2_2") (pintype "passive"))
      (node (ref "C33") (pin "2") (pinfunction "2_2") (pintype "passive"))
      (node (ref "C45") (pin "2") (pinfunction "2_2") (pintype "passive"))
      (node (ref "C46") (pin "2") (pinfunction "2_2") (pintype "passive"))
      (node (ref "R10") (pin "2") (pinfunction "2_2") (pintype "passive"))
      (node (ref "R11") (pin "2") (pinfunction "2_2") (pintype "passive"))
      (node (ref "R12") (pin "2") (pinfunction "2_2") (pintype "passive"))
      (node (ref "R13") (pin "3") (pinfunction "3_3") (pintype "passive"))
      (node (ref "R14") (pin "3") (pinfunction "3_3") (pintype "passive"))
      (node (ref "R15") (pin "3") (pinfunction "3_3") (pintype "passive"))
      (node (ref "R25") (pin "2") (pinfunction "2_2") (pintype "passive"))
      (node (ref "R26") (pin "2") (pinfunction "2_2") (pintype "passive"))
      (node (ref "R27") (pin "2") (pinfunction "2_2") (pintype "passive"))
      (node (ref "R28") (pin "3") (pinfunction "3_3") (pintype "passive"))
      (node (ref "R29") (pin "3") (pinfunction "3_3") (pintype "passive"))
      (node (ref "R30") (pin "3") (pinfunction "3_3") (pintype "passive"))
      (node (ref "R37") (pin "2") (pinfunction "2_2") (pintype "passive"))
      (node (ref "R38") (pin "2") (pinfunction "2_2") (pintype "passive"))
      (node (ref "R39") (pin "3") (pinfunction "3_3") (pintype "passive"))
      (node (ref "R40") (pin "3") (pinfunction "3_3") (pintype "passive"))
      (node (ref "U1") (pin "15") (pinfunction "V3P3OUT_15") (pintype "passive"))
      (node (ref "U2") (pin "15") (pinfunction "V3P3OUT_15") (pintype "passive"))
      (node (ref "U3") (pin "15") (pinfunction "V3P3OUT_15") (pintype "passive"))
      (node (ref "U4") (pin "15") (pinfunction "V3P3OUT_15") (pintype "passive"))
      (node (ref "U5") (pin "15") (pinfunction "V3P3OUT_15") (pintype "passive"))
      (node (ref "U6") (pin "15") (pinfunction "V3P3OUT_15") (pintype "passive"))
      (node (ref "U7") (pin "15") (pinfunction "V3P3OUT_15") (pintype "passive"))
      (node (ref "U8") (pin "15") (pinfunction "V3P3OUT_15") (pintype "passive"))
    )
    (net (code "125") (name "VM") (class "Default")
      (node (ref "C10") (pin "1") (pinfunction "1_1") (pintype "passive"))
      (node (ref "C11") (pin "1") (pinfunction "1_1") (pintype "passive"))
      (node (ref "C12") (pin "1") (pinfunction "1_1") (pintype "passive"))
      (node (ref "C13") (pin "2") (pinfunction "2_2") (pintype "passive"))
      (node (ref "C17") (pin "2") (pinfunction "2_2") (pintype "passive"))
      (node (ref "C18") (pin "2") (pinfunction "2_2") (pintype "passive"))
      (node (ref "C22") (pin "2") (pinfunction "2_2") (pintype "passive"))
      (node (ref "C23") (pin "2") (pinfunction "2_2") (pintype "passive"))
      (node (ref "C24") (pin "2") (pinfunction "2_2") (pintype "passive"))
      (node (ref "C25") (pin "2") (pinfunction "2_2") (pintype "passive"))
      (node (ref "C26") (pin "2") (pinfunction "2_2") (pintype "passive"))
      (node (ref "C27") (pin "2") (pinfunction "2_2") (pintype "passive"))
      (node (ref "C28") (pin "1") (pinfunction "1_1") (pintype "passive"))
      (node (ref "C29") (pin "1") (pinfunction "1_1") (pintype "passive"))
      (node (ref "C30") (pin "1") (pinfunction "1_1") (pintype "passive"))
      (node (ref "C34") (pin "2") (pinfunction "2_2") (pintype "passive"))
      (node (ref "C35") (pin "2") (pinfunction "2_2") (pintype "passive"))
      (node (ref "C36") (pin "2") (pinfunction "2_2") (pintype "passive"))
      (node (ref "C39") (pin "2") (pinfunction "2_2") (pintype "passive"))
      (node (ref "C4") (pin "2") (pinfunction "2_2") (pintype "passive"))
      (node (ref "C40") (pin "2") (pinfunction "2_2") (pintype "passive"))
      (node (ref "C41") (pin "2") (pinfunction "2_2") (pintype "passive"))
      (node (ref "C42") (pin "2") (pinfunction "2_2") (pintype "passive"))
      (node (ref "C43") (pin "1") (pinfunction "1_1") (pintype "passive"))
      (node (ref "C44") (pin "1") (pinfunction "1_1") (pintype "passive"))
      (node (ref "C47") (pin "2") (pinfunction "2_2") (pintype "passive"))
      (node (ref "C48") (pin "2") (pinfunction "2_2") (pintype "passive"))
      (node (ref "C5") (pin "2") (pinfunction "2_2") (pintype "passive"))
      (node (ref "C6") (pin "2") (pinfunction "2_2") (pintype "passive"))
      (node (ref "C7") (pin "2") (pinfunction "2_2") (pintype "passive"))
      (node (ref "C8") (pin "2") (pinfunction "2_2") (pintype "passive"))
      (node (ref "C9") (pin "2") (pinfunction "2_2") (pintype "passive"))
      (node (ref "R1") (pin "1") (pinfunction "1_1") (pintype "passive"))
      (node (ref "R16") (pin "1") (pinfunction "1_1") (pintype "passive"))
      (node (ref "R17") (pin "1") (pinfunction "1_1") (pintype "passive"))
      (node (ref "R18") (pin "1") (pinfunction "1_1") (pintype "passive"))
      (node (ref "R2") (pin "1") (pinfunction "1_1") (pintype "passive"))
      (node (ref "R3") (pin "1") (pinfunction "1_1") (pintype "passive"))
      (node (ref "R31") (pin "1") (pinfunction "1_1") (pintype "passive"))
      (node (ref "R32") (pin "1") (pinfunction "1_1") (pintype "passive"))
      (node (ref "U1") (pin "11") (pinfunction "VMB_11") (pintype "passive"))
      (node (ref "U1") (pin "4") (pinfunction "VMA_4") (pintype "passive"))
      (node (ref "U2") (pin "11") (pinfunction "VMB_11") (pintype "passive"))
      (node (ref "U2") (pin "4") (pinfunction "VMA_4") (pintype "passive"))
      (node (ref "U3") (pin "11") (pinfunction "VMB_11") (pintype "passive"))
      (node (ref "U3") (pin "4") (pinfunction "VMA_4") (pintype "passive"))
      (node (ref "U4") (pin "11") (pinfunction "VMB_11") (pintype "passive"))
      (node (ref "U4") (pin "4") (pinfunction "VMA_4") (pintype "passive"))
      (node (ref "U5") (pin "11") (pinfunction "VMB_11") (pintype "passive"))
      (node (ref "U5") (pin "4") (pinfunction "VMA_4") (pintype "passive"))
      (node (ref "U6") (pin "11") (pinfunction "VMB_11") (pintype "passive"))
      (node (ref "U6") (pin "4") (pinfunction "VMA_4") (pintype "passive"))
      (node (ref "U7") (pin "11") (pinfunction "VMB_11") (pintype "passive"))
      (node (ref "U7") (pin "4") (pinfunction "VMA_4") (pintype "passive"))
      (node (ref "U8") (pin "11") (pinfunction "VMB_11") (pintype "passive"))
      (node (ref "U8") (pin "4") (pinfunction "VMA_4") (pintype "passive"))
    )
    (net (code "126") (name "unconnected-(CN1-Pad5)") (class "Default")
      (node (ref "CN1") (pin "5") (pinfunction "5_5") (pintype "passive+no_connect"))
    )
    (net (code "127") (name "unconnected-(CN1-Pad6)") (class "Default")
      (node (ref "CN1") (pin "6") (pinfunction "6_6") (pintype "passive+no_connect"))
    )
    (net (code "128") (name "unconnected-(CN2-Pad5)") (class "Default")
      (node (ref "CN2") (pin "5") (pinfunction "5_5") (pintype "passive+no_connect"))
    )
    (net (code "129") (name "unconnected-(CN2-Pad6)") (class "Default")
      (node (ref "CN2") (pin "6") (pinfunction "6_6") (pintype "passive+no_connect"))
    )
    (net (code "130") (name "unconnected-(CN3-Pad5)") (class "Default")
      (node (ref "CN3") (pin "5") (pinfunction "5_5") (pintype "passive+no_connect"))
    )
    (net (code "131") (name "unconnected-(CN3-Pad6)") (class "Default")
      (node (ref "CN3") (pin "6") (pinfunction "6_6") (pintype "passive+no_connect"))
    )
    (net (code "132") (name "unconnected-(CN4-Pad5)") (class "Default")
      (node (ref "CN4") (pin "5") (pinfunction "5_5") (pintype "passive+no_connect"))
    )
    (net (code "133") (name "unconnected-(CN4-Pad6)") (class "Default")
      (node (ref "CN4") (pin "6") (pinfunction "6_6") (pintype "passive+no_connect"))
    )
    (net (code "134") (name "unconnected-(CN5-Pad5)") (class "Default")
      (node (ref "CN5") (pin "5") (pinfunction "5_5") (pintype "passive+no_connect"))
    )
    (net (code "135") (name "unconnected-(CN5-Pad6)") (class "Default")
      (node (ref "CN5") (pin "6") (pinfunction "6_6") (pintype "passive+no_connect"))
    )
    (net (code "136") (name "unconnected-(CN6-Pad5)") (class "Default")
      (node (ref "CN6") (pin "5") (pinfunction "5_5") (pintype "passive+no_connect"))
    )
    (net (code "137") (name "unconnected-(CN6-Pad6)") (class "Default")
      (node (ref "CN6") (pin "6") (pinfunction "6_6") (pintype "passive+no_connect"))
    )
    (net (code "138") (name "unconnected-(CN7-Pad5)") (class "Default")
      (node (ref "CN7") (pin "5") (pinfunction "5_5") (pintype "passive+no_connect"))
    )
    (net (code "139") (name "unconnected-(CN7-Pad6)") (class "Default")
      (node (ref "CN7") (pin "6") (pinfunction "6_6") (pintype "passive+no_connect"))
    )
    (net (code "140") (name "unconnected-(CN8-Pad5)") (class "Default")
      (node (ref "CN8") (pin "5") (pinfunction "5_5") (pintype "passive+no_connect"))
    )
    (net (code "141") (name "unconnected-(CN8-Pad6)") (class "Default")
      (node (ref "CN8") (pin "6") (pinfunction "6_6") (pintype "passive+no_connect"))
    )
    (net (code "142") (name "unconnected-(U1-DECAY-Pad19)") (class "Default")
      (node (ref "U1") (pin "19") (pinfunction "DECAY_19") (pintype "passive+no_connect"))
    )
    (net (code "143") (name "unconnected-(U1-NC-Pad23)") (class "Default")
      (node (ref "U1") (pin "23") (pinfunction "NC_23") (pintype "passive+no_connect"))
    )
    (net (code "144") (name "unconnected-(U1-nHOME-Pad27)") (class "Default")
      (node (ref "U1") (pin "27") (pinfunction "nHOME_27") (pintype "passive+no_connect"))
    )
    (net (code "145") (name "unconnected-(U2-DECAY-Pad19)") (class "Default")
      (node (ref "U2") (pin "19") (pinfunction "DECAY_19") (pintype "passive+no_connect"))
    )
    (net (code "146") (name "unconnected-(U2-NC-Pad23)") (class "Default")
      (node (ref "U2") (pin "23") (pinfunction "NC_23") (pintype "passive+no_connect"))
    )
    (net (code "147") (name "unconnected-(U2-nHOME-Pad27)") (class "Default")
      (node (ref "U2") (pin "27") (pinfunction "nHOME_27") (pintype "passive+no_connect"))
    )
    (net (code "148") (name "unconnected-(U3-DECAY-Pad19)") (class "Default")
      (node (ref "U3") (pin "19") (pinfunction "DECAY_19") (pintype "passive+no_connect"))
    )
    (net (code "149") (name "unconnected-(U3-NC-Pad23)") (class "Default")
      (node (ref "U3") (pin "23") (pinfunction "NC_23") (pintype "passive+no_connect"))
    )
    (net (code "150") (name "unconnected-(U3-nHOME-Pad27)") (class "Default")
      (node (ref "U3") (pin "27") (pinfunction "nHOME_27") (pintype "passive+no_connect"))
    )
    (net (code "151") (name "unconnected-(U4-DECAY-Pad19)") (class "Default")
      (node (ref "U4") (pin "19") (pinfunction "DECAY_19") (pintype "passive+no_connect"))
    )
    (net (code "152") (name "unconnected-(U4-NC-Pad23)") (class "Default")
      (node (ref "U4") (pin "23") (pinfunction "NC_23") (pintype "passive+no_connect"))
    )
    (net (code "153") (name "unconnected-(U4-nHOME-Pad27)") (class "Default")
      (node (ref "U4") (pin "27") (pinfunction "nHOME_27") (pintype "passive+no_connect"))
    )
    (net (code "154") (name "unconnected-(U5-DECAY-Pad19)") (class "Default")
      (node (ref "U5") (pin "19") (pinfunction "DECAY_19") (pintype "passive+no_connect"))
    )
    (net (code "155") (name "unconnected-(U5-NC-Pad23)") (class "Default")
      (node (ref "U5") (pin "23") (pinfunction "NC_23") (pintype "passive+no_connect"))
    )
    (net (code "156") (name "unconnected-(U5-nHOME-Pad27)") (class "Default")
      (node (ref "U5") (pin "27") (pinfunction "nHOME_27") (pintype "passive+no_connect"))
    )
    (net (code "157") (name "unconnected-(U6-DECAY-Pad19)") (class "Default")
      (node (ref "U6") (pin "19") (pinfunction "DECAY_19") (pintype "passive+no_connect"))
    )
    (net (code "158") (name "unconnected-(U6-NC-Pad23)") (class "Default")
      (node (ref "U6") (pin "23") (pinfunction "NC_23") (pintype "passive+no_connect"))
    )
    (net (code "159") (name "unconnected-(U6-nHOME-Pad27)") (class "Default")
      (node (ref "U6") (pin "27") (pinfunction "nHOME_27") (pintype "passive+no_connect"))
    )
    (net (code "160") (name "unconnected-(U7-DECAY-Pad19)") (class "Default")
      (node (ref "U7") (pin "19") (pinfunction "DECAY_19") (pintype "passive+no_connect"))
    )
    (net (code "161") (name "unconnected-(U7-NC-Pad23)") (class "Default")
      (node (ref "U7") (pin "23") (pinfunction "NC_23") (pintype "passive+no_connect"))
    )
    (net (code "162") (name "unconnected-(U7-nHOME-Pad27)") (class "Default")
      (node (ref "U7") (pin "27") (pinfunction "nHOME_27") (pintype "passive+no_connect"))
    )
    (net (code "163") (name "unconnected-(U8-DECAY-Pad19)") (class "Default")
      (node (ref "U8") (pin "19") (pinfunction "DECAY_19") (pintype "passive+no_connect"))
    )
    (net (code "164") (name "unconnected-(U8-NC-Pad23)") (class "Default")
      (node (ref "U8") (pin "23") (pinfunction "NC_23") (pintype "passive+no_connect"))
    )
    (net (code "165") (name "unconnected-(U8-nHOME-Pad27)") (class "Default")
      (node (ref "U8") (pin "27") (pinfunction "nHOME_27") (pintype "passive+no_connect"))
    )
  )
)
